# logmega_083.net
KiCad netlist of a schematic drawn in EAGLE
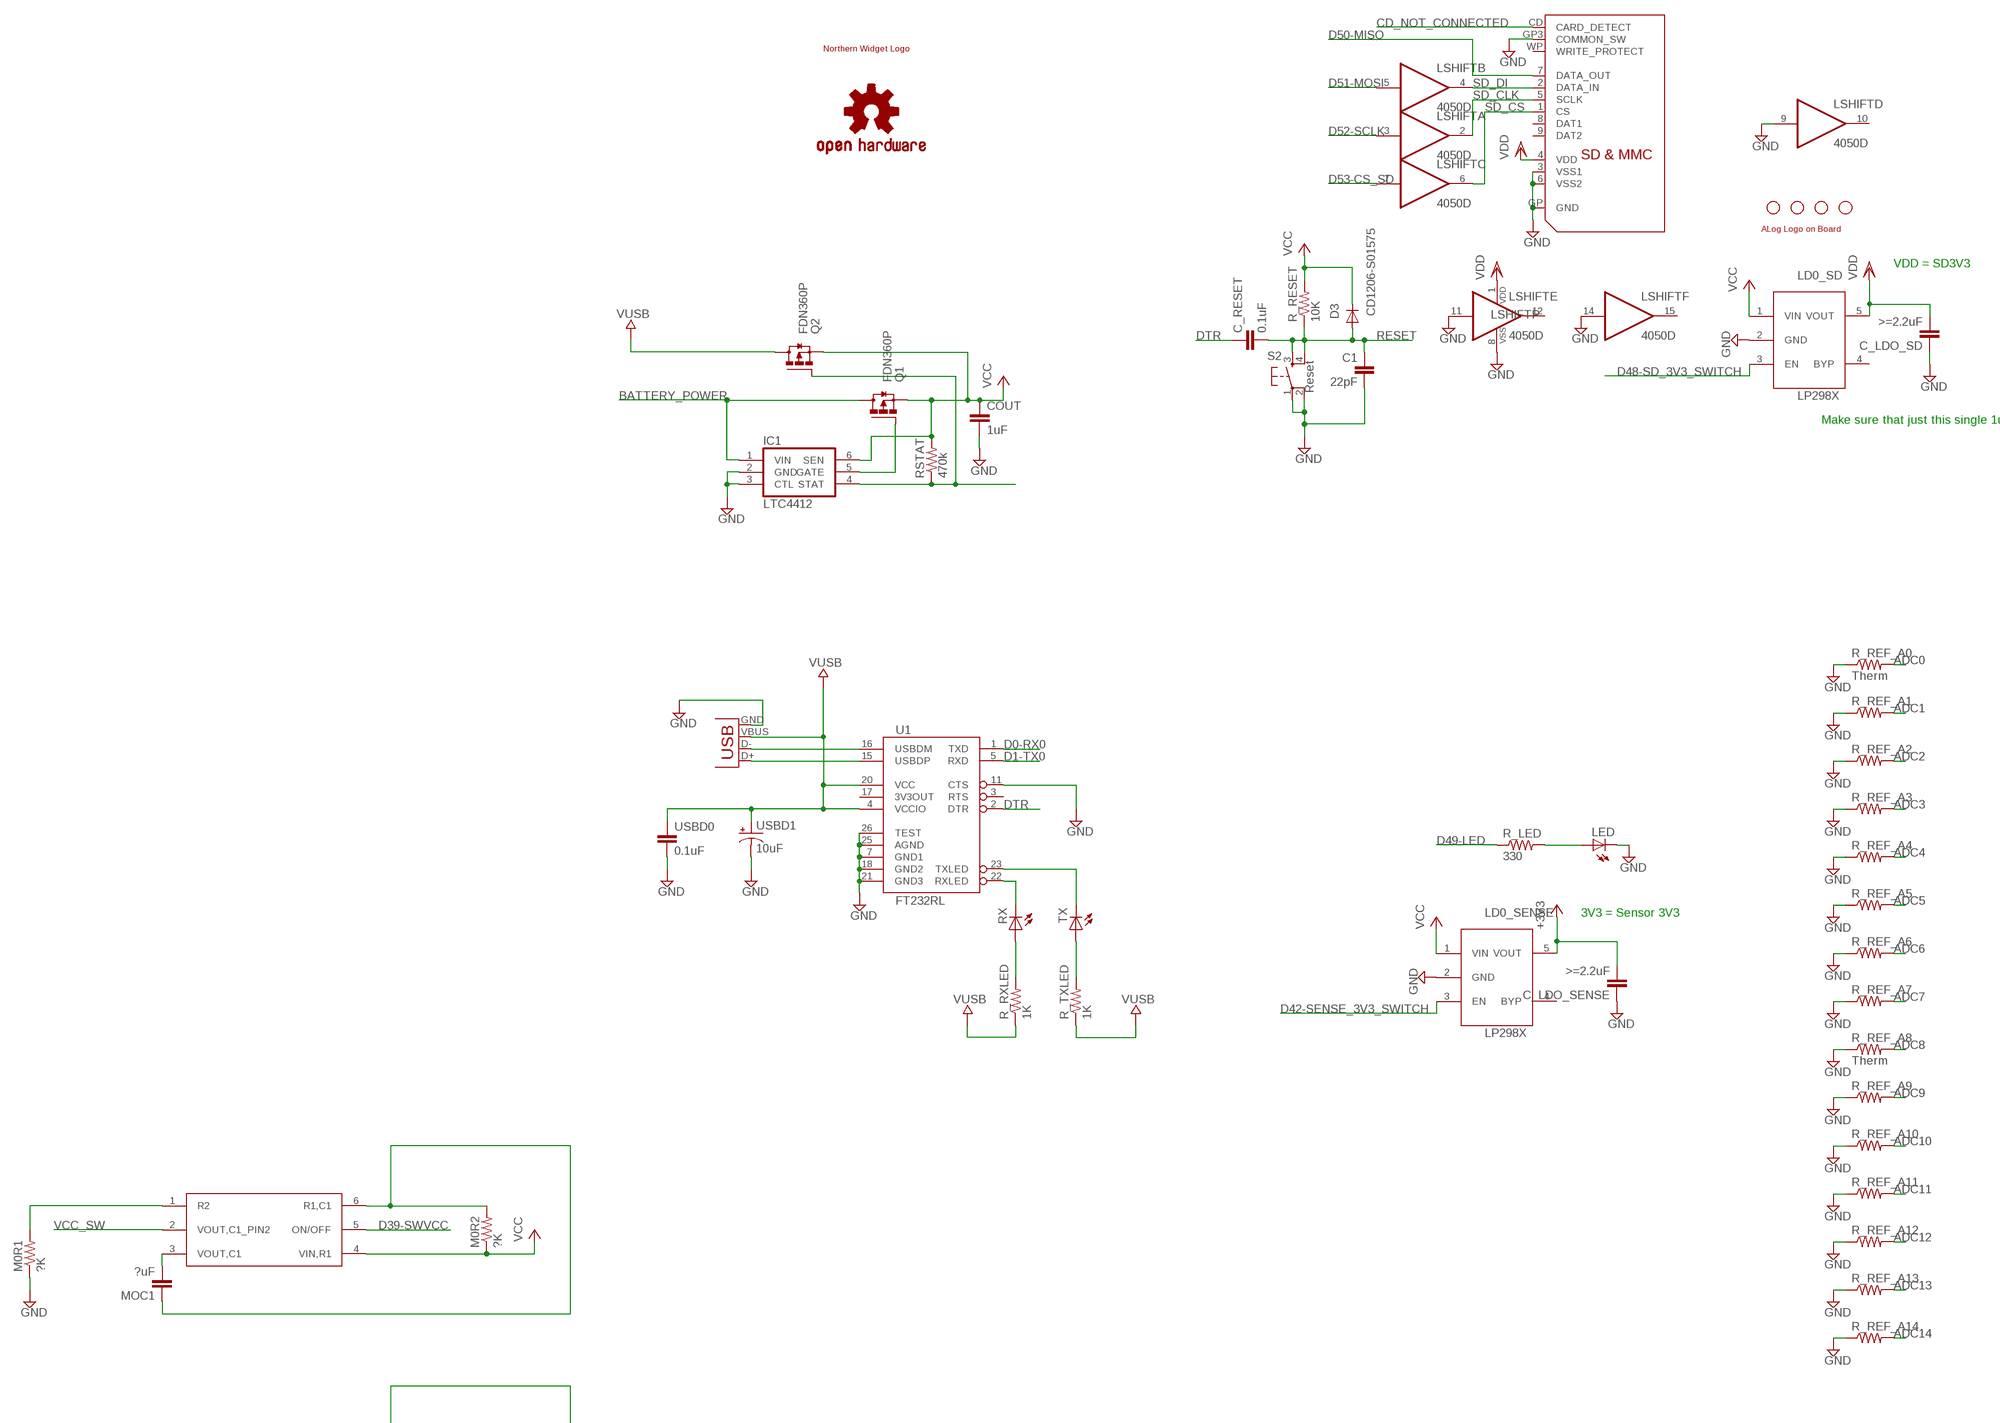
[diagram p0: schematic, sheet 1, part 1 of 3]
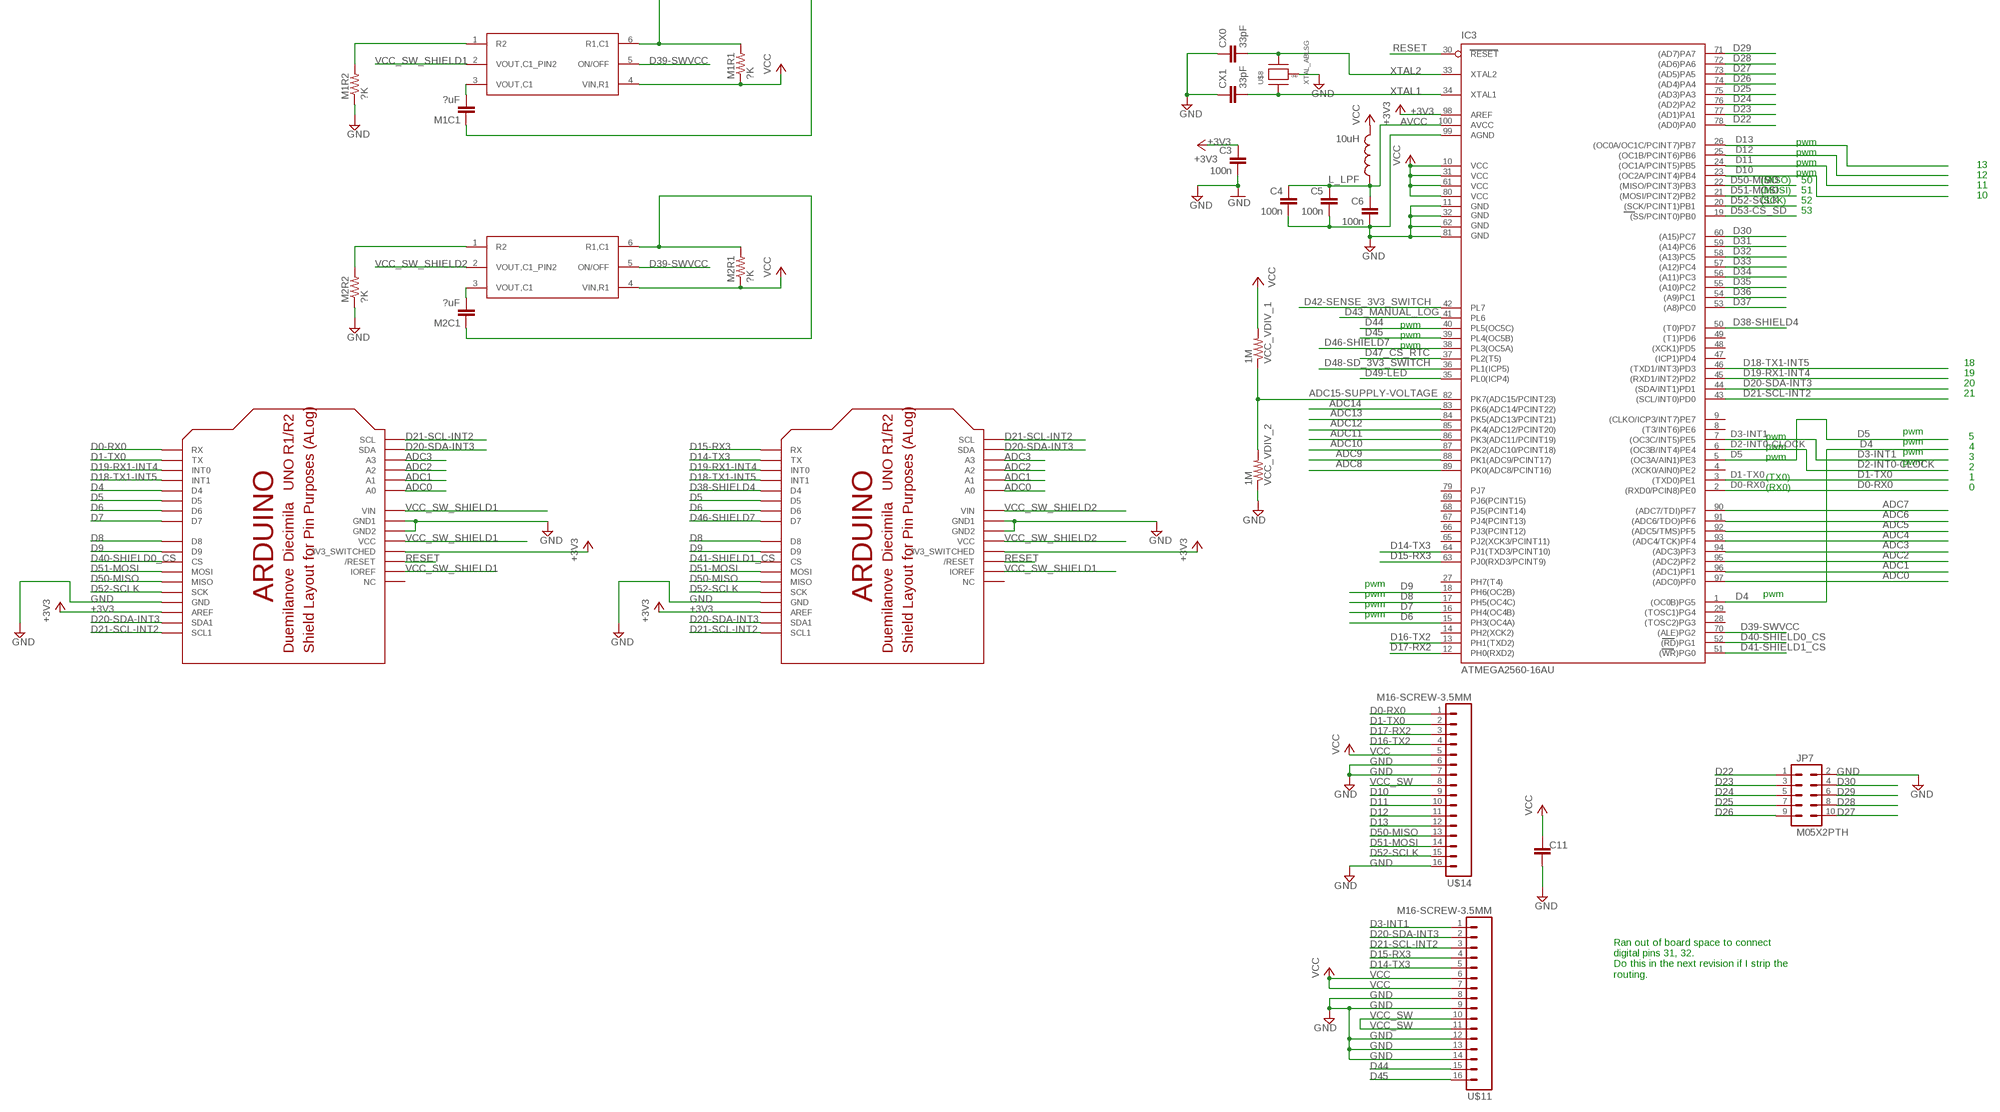
[diagram p1: schematic, sheet 1, part 2 of 3]
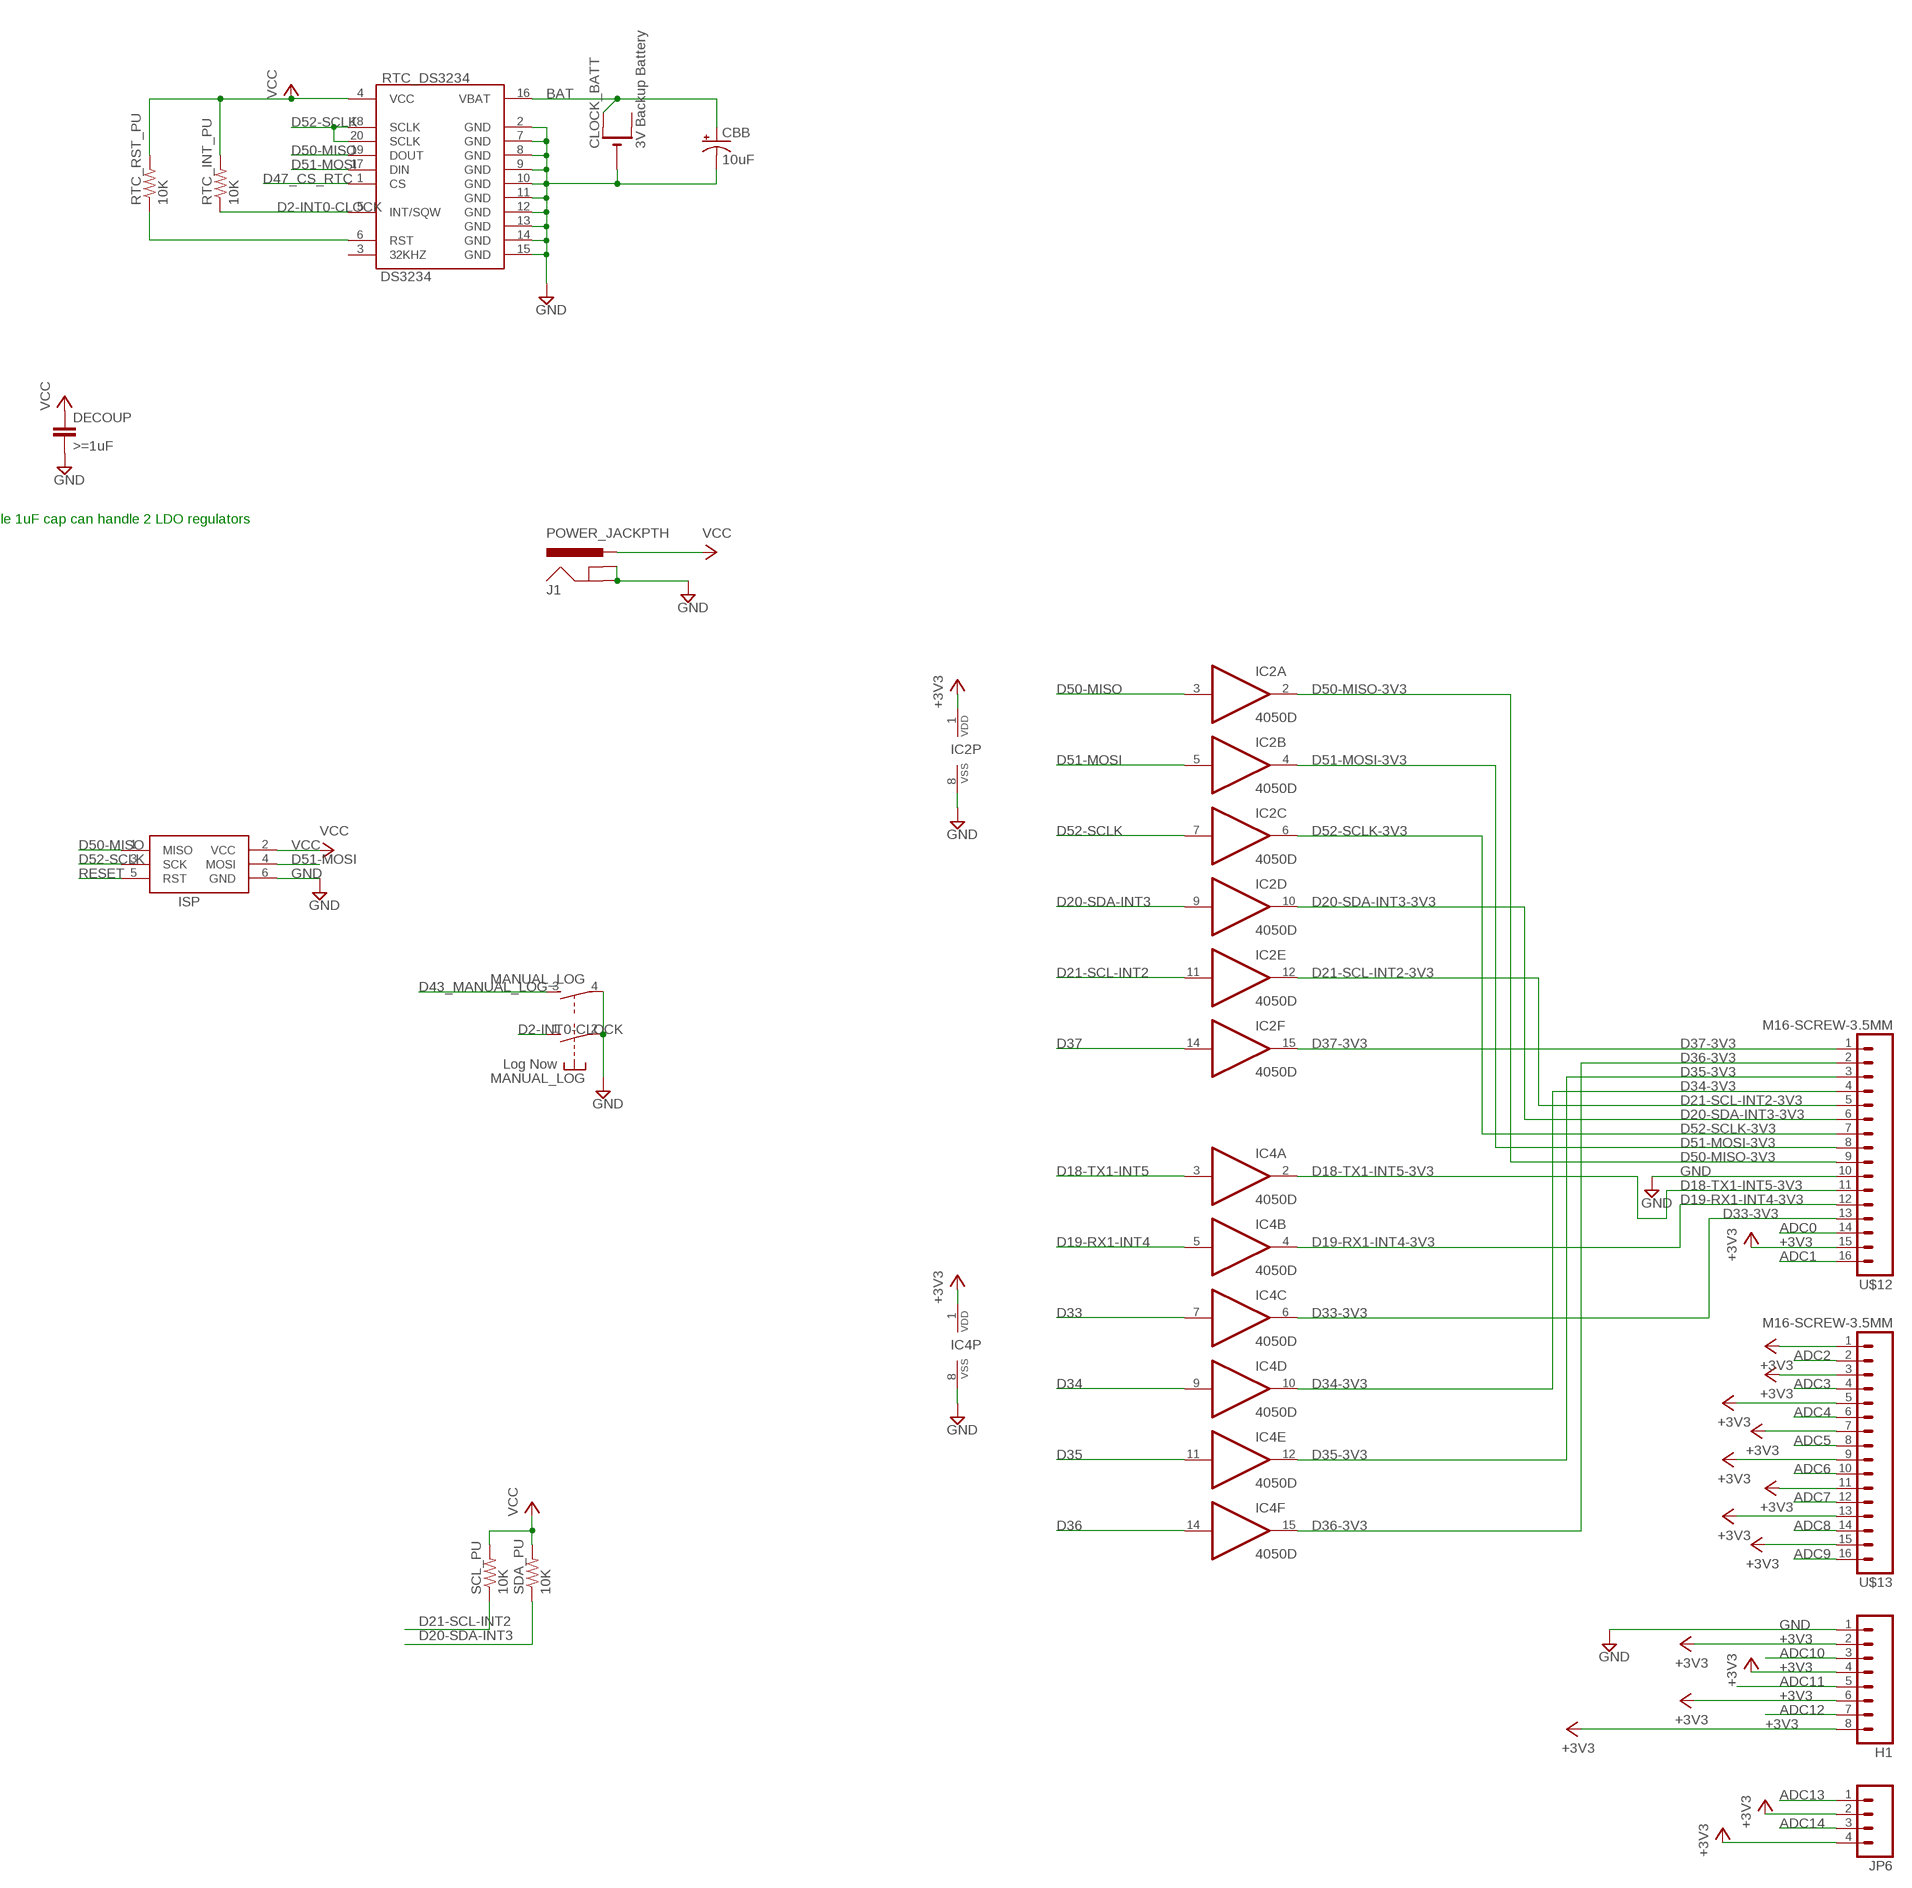
[diagram p2: schematic, sheet 1, part 3 of 3]

(export (version "E")
  (design (tool "Eeschema 10.0.6"))
  (components
    (comp (ref "C1")
      (value "22pF")
      (footprint "eagle-import:C0603-ROUND")
      (libsource (lib "eagle-import") (part "C-EU0603-RND"))
    )
    (comp (ref "C3")
      (value "100n")
      (footprint "eagle-import:C0603-ROUND")
      (libsource (lib "eagle-import") (part "C-EU0603-RND"))
    )
    (comp (ref "C4")
      (value "100n")
      (footprint "eagle-import:C0603-ROUND")
      (libsource (lib "eagle-import") (part "C-EU0603-RND"))
    )
    (comp (ref "C5")
      (value "100n")
      (footprint "eagle-import:C0603-ROUND")
      (libsource (lib "eagle-import") (part "C-EU0603-RND"))
    )
    (comp (ref "C6")
      (value "100n")
      (footprint "eagle-import:C0603-ROUND")
      (libsource (lib "eagle-import") (part "C-EU0603-RND"))
    )
    (comp (ref "C11")
      (value "100n")
      (footprint "eagle-import:C0603-ROUND")
      (libsource (lib "eagle-import") (part "C-EU0603-RND"))
    )
    (comp (ref "CBB")
      (value "10uF")
      (footprint "eagle-import:EIA3216")
      (libsource (lib "eagle-import") (part "CAP_POL1206"))
    )
    (comp (ref "CLOCK_BATT")
      (value "3V Backup Battery")
      (footprint "eagle-import:CR2032-SMD")
      (libsource (lib "eagle-import") (part "CR2032SMT"))
    )
    (comp (ref "COUT")
      (value "1uF")
      (footprint "eagle-import:C0603-ROUND")
      (libsource (lib "eagle-import") (part "C-EUC0603"))
    )
    (comp (ref "CX0")
      (value "33pF")
      (footprint "eagle-import:C0603")
      (libsource (lib "eagle-import") (part "resistor_C-EUC0603"))
    )
    (comp (ref "CX1")
      (value "33pF")
      (footprint "eagle-import:C0603")
      (libsource (lib "eagle-import") (part "resistor_C-EUC0603"))
    )
    (comp (ref "C_LDO_SD")
      (value ">=2.2uF")
      (footprint "eagle-import:C0603")
      (libsource (lib "eagle-import") (part "resistor_C-EUC0603"))
    )
    (comp (ref "C_LDO_SENSE")
      (value ">=2.2uF")
      (footprint "eagle-import:C0603")
      (libsource (lib "eagle-import") (part "resistor_C-EUC0603"))
    )
    (comp (ref "C_RESET")
      (value "0.1uF")
      (footprint "eagle-import:C0603")
      (libsource (lib "eagle-import") (part "resistor_C-EUC0603"))
    )
    (comp (ref "D3")
      (value "CD1206-S01575")
      (footprint "eagle-import:MINIMELF")
      (libsource (lib "eagle-import") (part "DIODE-MINIMELF"))
    )
    (comp (ref "DECOUP")
      (value ">=1uF")
      (footprint "eagle-import:C0603")
      (libsource (lib "eagle-import") (part "resistor_C-EUC0603"))
    )
    (comp (ref "H1")
      (value "M083.5MM-8")
      (footprint "eagle-import:SCREWTERMINAL-3.5MM-8")
      (libsource (lib "eagle-import") (part "M083.5MM-8"))
    )
    (comp (ref "IC1")
      (value "LTC4412")
      (footprint "eagle-import:TSOT23-6")
      (libsource (lib "eagle-import") (part "LTC4412S6E"))
    )
    (comp (ref "IC2")
      (value "4050D")
      (footprint "eagle-import:SO16")
      (libsource (lib "eagle-import") (part "4050D"))
    )
    (comp (ref "IC3")
      (value "ATMEGA2560-16AU")
      (footprint "eagle-import:TQFP100")
      (libsource (lib "eagle-import") (part "ATMEGA2560AU2560-16"))
    )
    (comp (ref "IC4")
      (value "4050D")
      (footprint "eagle-import:SO16")
      (libsource (lib "eagle-import") (part "4050D"))
    )
    (comp (ref "ISP")
      (value "AVRISP-6")
      (footprint "eagle-import:AVRISP")
      (libsource (lib "eagle-import") (part "AVRISP-6"))
    )
    (comp (ref "J1")
      (value "POWER_JACKPTH")
      (footprint "eagle-import:POWER_JACK_PTH")
      (libsource (lib "eagle-import") (part "POWER_JACKPTH"))
    )
    (comp (ref "JP1")
      (value "STAND-OFF")
      (footprint "eagle-import:STAND-OFF")
      (libsource (lib "eagle-import") (part "STAND-OFF"))
    )
    (comp (ref "JP2")
      (value "STAND-OFF")
      (footprint "eagle-import:STAND-OFF")
      (libsource (lib "eagle-import") (part "STAND-OFF"))
    )
    (comp (ref "JP3")
      (value "STAND-OFF")
      (footprint "eagle-import:STAND-OFF")
      (libsource (lib "eagle-import") (part "STAND-OFF"))
    )
    (comp (ref "JP4")
      (value "STAND-OFF")
      (footprint "eagle-import:STAND-OFF")
      (libsource (lib "eagle-import") (part "STAND-OFF"))
    )
    (comp (ref "JP5")
      (value "USB-B")
      (footprint "eagle-import:USB-B-PTH")
      (libsource (lib "eagle-import") (part "USBPTH"))
    )
    (comp (ref "JP6")
      (value "M04SCREW")
      (footprint "eagle-import:SCREWTERMINAL-3.5MM-4")
      (libsource (lib "eagle-import") (part "M04SCREW"))
    )
    (comp (ref "JP7")
      (value "M05X2PTH")
      (footprint "eagle-import:AVR_ICSP")
      (libsource (lib "eagle-import") (part "M05X2PTH"))
    )
    (comp (ref "LD0_SD")
      (value "LP2985")
      (footprint "eagle-import:SOT23-5L")
      (libsource (lib "eagle-import") (part "LP298XS"))
    )
    (comp (ref "LD0_SENSE")
      (value "LP2985")
      (footprint "eagle-import:SOT23-5L")
      (libsource (lib "eagle-import") (part "LP298XS"))
    )
    (comp (ref "LED")
      (value "LED3MM")
      (footprint "eagle-import:LED3MM")
      (libsource (lib "eagle-import") (part "LED3MM"))
    )
    (comp (ref "LOGO1")
      (value "OSHW-LOGOM")
      (footprint "eagle-import:OSHW-LOGO-M")
      (libsource (lib "eagle-import") (part "OSHW-LOGOM"))
    )
    (comp (ref "LSHIFT")
      (value "4050D")
      (footprint "eagle-import:SO16")
      (libsource (lib "eagle-import") (part "4050D"))
    )
    (comp (ref "L_LPF")
      (value "10uH")
      (footprint "eagle-import:0805")
      (libsource (lib "eagle-import") (part "INDUCTOR0805"))
    )
    (comp (ref "M0R1")
      (value "?K")
      (footprint "eagle-import:R0603")
      (libsource (lib "eagle-import") (part "R-US_R0603"))
    )
    (comp (ref "M0R2")
      (value "?K")
      (footprint "eagle-import:R0603")
      (libsource (lib "eagle-import") (part "R-US_R0603"))
    )
    (comp (ref "M1")
      (value "FDG6342L")
      (footprint "eagle-import:SOT-363")
      (libsource (lib "eagle-import") (part "FDG6342L"))
    )
    (comp (ref "M1C1")
      (value "?uF")
      (footprint "eagle-import:C0603")
      (libsource (lib "eagle-import") (part "resistor_C-EUC0603"))
    )
    (comp (ref "M1R1")
      (value "?K")
      (footprint "eagle-import:R0603")
      (libsource (lib "eagle-import") (part "R-US_R0603"))
    )
    (comp (ref "M1R2")
      (value "?K")
      (footprint "eagle-import:R0603")
      (libsource (lib "eagle-import") (part "R-US_R0603"))
    )
    (comp (ref "M2")
      (value "FDG6342L")
      (footprint "eagle-import:SOT-363")
      (libsource (lib "eagle-import") (part "FDG6342L"))
    )
    (comp (ref "M2C1")
      (value "?uF")
      (footprint "eagle-import:C0603")
      (libsource (lib "eagle-import") (part "resistor_C-EUC0603"))
    )
    (comp (ref "M2R1")
      (value "?K")
      (footprint "eagle-import:R0603")
      (libsource (lib "eagle-import") (part "R-US_R0603"))
    )
    (comp (ref "M2R2")
      (value "?K")
      (footprint "eagle-import:R0603")
      (libsource (lib "eagle-import") (part "R-US_R0603"))
    )
    (comp (ref "MANUAL_LOG")
      (value "Log Now")
      (footprint "eagle-import:PVA1F")
      (libsource (lib "eagle-import") (part "PVA1"))
    )
    (comp (ref "MOC1")
      (value "?uF")
      (footprint "eagle-import:C0603")
      (libsource (lib "eagle-import") (part "resistor_C-EUC0603"))
    )
    (comp (ref "Q1")
      (value "FDN360P")
      (footprint "eagle-import:SUPER-SOT3")
      (libsource (lib "eagle-import") (part "FDN360P"))
    )
    (comp (ref "Q2")
      (value "FDN360P")
      (footprint "eagle-import:SUPER-SOT3")
      (libsource (lib "eagle-import") (part "FDN360P"))
    )
    (comp (ref "RSTAT")
      (value "470k")
      (footprint "eagle-import:R0603")
      (libsource (lib "eagle-import") (part "R-US_R0603"))
    )
    (comp (ref "RTC_DS3234")
      (value "DS3234")
      (footprint "eagle-import:DS3234")
      (libsource (lib "eagle-import") (part "DS3234"))
    )
    (comp (ref "RTC_INT_PU")
      (value "10K")
      (footprint "eagle-import:R0603")
      (libsource (lib "eagle-import") (part "R-US_R0603"))
    )
    (comp (ref "RTC_RST_PU")
      (value "10K")
      (footprint "eagle-import:R0603")
      (libsource (lib "eagle-import") (part "R-US_R0603"))
    )
    (comp (ref "RX")
      (value "LED0603")
      (footprint "eagle-import:LED-0603")
      (libsource (lib "eagle-import") (part "SparkFun-LED_LED0603"))
    )
    (comp (ref "R_LED")
      (value "330")
      (footprint "eagle-import:R0603")
      (libsource (lib "eagle-import") (part "R-US_R0603"))
    )
    (comp (ref "R_REF_A0")
      (value "Therm")
      (footprint "eagle-import:0207_10")
      (libsource (lib "eagle-import") (part "resistor_R-US_0207/10"))
    )
    (comp (ref "R_REF_A1")
      (value "R-US_0207/10")
      (footprint "eagle-import:0207_10")
      (libsource (lib "eagle-import") (part "resistor_R-US_0207/10"))
    )
    (comp (ref "R_REF_A2")
      (value "R-US_0207/10")
      (footprint "eagle-import:0207_10")
      (libsource (lib "eagle-import") (part "resistor_R-US_0207/10"))
    )
    (comp (ref "R_REF_A3")
      (value "R-US_0207/10")
      (footprint "eagle-import:0207_10")
      (libsource (lib "eagle-import") (part "resistor_R-US_0207/10"))
    )
    (comp (ref "R_REF_A4")
      (value "R-US_0207/10")
      (footprint "eagle-import:0207_10")
      (libsource (lib "eagle-import") (part "resistor_R-US_0207/10"))
    )
    (comp (ref "R_REF_A5")
      (value "R-US_0207/10")
      (footprint "eagle-import:0207_10")
      (libsource (lib "eagle-import") (part "resistor_R-US_0207/10"))
    )
    (comp (ref "R_REF_A6")
      (value "R-US_0207/10")
      (footprint "eagle-import:0207_10")
      (libsource (lib "eagle-import") (part "resistor_R-US_0207/10"))
    )
    (comp (ref "R_REF_A7")
      (value "R-US_0207/10")
      (footprint "eagle-import:0207_10")
      (libsource (lib "eagle-import") (part "resistor_R-US_0207/10"))
    )
    (comp (ref "R_REF_A8")
      (value "Therm")
      (footprint "eagle-import:0207_10")
      (libsource (lib "eagle-import") (part "resistor_R-US_0207/10"))
    )
    (comp (ref "R_REF_A9")
      (value "R-US_0207/10")
      (footprint "eagle-import:0207_10")
      (libsource (lib "eagle-import") (part "resistor_R-US_0207/10"))
    )
    (comp (ref "R_REF_A10")
      (value "R-US_0207/10")
      (footprint "eagle-import:0207_10")
      (libsource (lib "eagle-import") (part "resistor_R-US_0207/10"))
    )
    (comp (ref "R_REF_A11")
      (value "R-US_0207/10")
      (footprint "eagle-import:0207_10")
      (libsource (lib "eagle-import") (part "resistor_R-US_0207/10"))
    )
    (comp (ref "R_REF_A12")
      (value "R-US_0207/10")
      (footprint "eagle-import:0207_10")
      (libsource (lib "eagle-import") (part "resistor_R-US_0207/10"))
    )
    (comp (ref "R_REF_A13")
      (value "R-US_0207/10")
      (footprint "eagle-import:0207_10")
      (libsource (lib "eagle-import") (part "resistor_R-US_0207/10"))
    )
    (comp (ref "R_REF_A14")
      (value "R-US_0207/10")
      (footprint "eagle-import:0207_10")
      (libsource (lib "eagle-import") (part "resistor_R-US_0207/10"))
    )
    (comp (ref "R_RESET")
      (value "10K")
      (footprint "eagle-import:R0603")
      (libsource (lib "eagle-import") (part "R-US_R0603"))
    )
    (comp (ref "R_RXLED")
      (value "1K")
      (footprint "eagle-import:R0603")
      (libsource (lib "eagle-import") (part "R-US_R0603"))
    )
    (comp (ref "R_TXLED")
      (value "1K")
      (footprint "eagle-import:R0603")
      (libsource (lib "eagle-import") (part "R-US_R0603"))
    )
    (comp (ref "S2")
      (value "Reset")
      (footprint "eagle-import:TACTILE-PTH")
      (libsource (lib "eagle-import") (part "TAC_SWITCHPTH"))
    )
    (comp (ref "SCL_PU")
      (value "10K")
      (footprint "eagle-import:R0603")
      (libsource (lib "eagle-import") (part "R-US_R0603"))
    )
    (comp (ref "SD")
      (value "SDMMC06132")
      (footprint "eagle-import:06132")
      (libsource (lib "eagle-import") (part "SDMMC06132"))
    )
    (comp (ref "SDA_PU")
      (value "10K")
      (footprint "eagle-import:R0603")
      (libsource (lib "eagle-import") (part "R-US_R0603"))
    )
    (comp (ref "SW")
      (value "FDG6342L")
      (footprint "eagle-import:SOT-363")
      (libsource (lib "eagle-import") (part "FDG6342L"))
    )
    (comp (ref "TX")
      (value "LED0603")
      (footprint "eagle-import:LED-0603")
      (libsource (lib "eagle-import") (part "SparkFun-LED_LED0603"))
    )
    (comp (ref "U$1")
      (value "NWLOGO")
      (footprint "eagle-import:NWLOGO")
      (libsource (lib "eagle-import") (part "NWLOGO"))
    )
    (comp (ref "U$2")
      (value "ALOG_LOGO_V1_5.5MM")
      (footprint "eagle-import:ALOG_LOGO_V1_SMALL")
      (libsource (lib "eagle-import") (part "ALOG_LOGO_V1_5.5MM"))
    )
    (comp (ref "U$7")
      (value "ARDUINO_SHIELD_BIGLOG_2")
      (footprint "eagle-import:ARDUINO_SHIELD_PO_BL2")
      (libsource (lib "eagle-import") (part "ARDUINO_SHIELD_BIGLOG_2"))
    )
    (comp (ref "U$8")
      (value "XTAL_ABLSG")
      (footprint "eagle-import:AT49")
      (libsource (lib "eagle-import") (part "XTAL_ABLSG"))
    )
    (comp (ref "U$9")
      (value "ARDUINO_SHIELD_BIGLOG_1")
      (footprint "eagle-import:ARDUINO_SHIELD_PO_BL1")
      (libsource (lib "eagle-import") (part "ARDUINO_SHIELD_BIGLOG_1"))
    )
    (comp (ref "U$11")
      (value "M16-SCREW-3.5MM")
      (footprint "eagle-import:M16-SCREW-3.5MM")
      (libsource (lib "eagle-import") (part "M16-SCREW-3.5MM"))
    )
    (comp (ref "U$12")
      (value "M16-SCREW-3.5MM")
      (footprint "eagle-import:M16-SCREW-3.5MM")
      (libsource (lib "eagle-import") (part "M16-SCREW-3.5MM"))
    )
    (comp (ref "U$13")
      (value "M16-SCREW-3.5MM")
      (footprint "eagle-import:M16-SCREW-3.5MM")
      (libsource (lib "eagle-import") (part "M16-SCREW-3.5MM"))
    )
    (comp (ref "U$14")
      (value "M16-SCREW-3.5MM")
      (footprint "eagle-import:M16-SCREW-3.5MM")
      (libsource (lib "eagle-import") (part "M16-SCREW-3.5MM"))
    )
    (comp (ref "U1")
      (value "FT232RL")
      (footprint "eagle-import:SSOP28DB")
      (libsource (lib "eagle-import") (part "FT232RL-BASICSSOP"))
    )
    (comp (ref "USBD0")
      (value "0.1uF")
      (footprint "eagle-import:C0603")
      (libsource (lib "eagle-import") (part "resistor_C-EUC0603"))
    )
    (comp (ref "USBD1")
      (value "10uF")
      (footprint "eagle-import:EIA3216")
      (libsource (lib "eagle-import") (part "CAP_POL1206"))
    )
    (comp (ref "VCC_VDIV_1")
      (value "1M")
      (footprint "eagle-import:R0603")
      (libsource (lib "eagle-import") (part "R-US_R0603"))
    )
    (comp (ref "VCC_VDIV_2")
      (value "1M")
      (footprint "eagle-import:R0603")
      (libsource (lib "eagle-import") (part "R-US_R0603"))
    )
  )
  (nets
    (net (code "1") (name "+3V3") (class "Default")
      (node (ref "C3") (pin "1") (pinfunction "1_1") (pintype "passive"))
      (node (ref "C_LDO_SENSE") (pin "2") (pinfunction "2_2") (pintype "passive"))
      (node (ref "H1") (pin "2") (pinfunction "2_2") (pintype "passive"))
      (node (ref "H1") (pin "4") (pinfunction "4_4") (pintype "passive"))
      (node (ref "H1") (pin "6") (pinfunction "6_6") (pintype "passive"))
      (node (ref "H1") (pin "8") (pinfunction "8_8") (pintype "passive"))
      (node (ref "IC2") (pin "1") (pinfunction "VDD_1") (pintype "power_in"))
      (node (ref "IC3") (pin "98") (pinfunction "AREF_98") (pintype "bidirectional"))
      (node (ref "IC4") (pin "1") (pinfunction "VDD_1") (pintype "power_in"))
      (node (ref "JP6") (pin "2") (pinfunction "2_2") (pintype "passive"))
      (node (ref "JP6") (pin "4") (pinfunction "4_4") (pintype "passive"))
      (node (ref "LD0_SENSE") (pin "5") (pinfunction "VOUT_5") (pintype "bidirectional"))
      (node (ref "U$12") (pin "15") (pinfunction "15_15") (pintype "passive"))
      (node (ref "U$13") (pin "1") (pinfunction "1_1") (pintype "passive"))
      (node (ref "U$13") (pin "11") (pinfunction "11_11") (pintype "passive"))
      (node (ref "U$13") (pin "13") (pinfunction "13_13") (pintype "passive"))
      (node (ref "U$13") (pin "15") (pinfunction "15_15") (pintype "passive"))
      (node (ref "U$13") (pin "3") (pinfunction "3_3") (pintype "passive"))
      (node (ref "U$13") (pin "5") (pinfunction "5_5") (pintype "passive"))
      (node (ref "U$13") (pin "7") (pinfunction "7_7") (pintype "passive"))
      (node (ref "U$13") (pin "9") (pinfunction "9_9") (pintype "passive"))
      (node (ref "U$7") (pin "3.3V") (pinfunction "3V3_SWITCHED_3.3V") (pintype "power_in"))
      (node (ref "U$7") (pin "AREF") (pinfunction "AREF_AREF") (pintype "bidirectional"))
      (node (ref "U$9") (pin "3.3V") (pinfunction "3V3_SWITCHED_3.3V") (pintype "power_in"))
      (node (ref "U$9") (pin "AREF") (pinfunction "AREF_AREF") (pintype "bidirectional"))
    )
    (net (code "2") (name "/ADC0") (class "Default")
      (node (ref "IC3") (pin "97") (pinfunction "(ADC0)PF0_97") (pintype "bidirectional"))
      (node (ref "R_REF_A0") (pin "2") (pinfunction "2_2") (pintype "passive"))
      (node (ref "U$12") (pin "14") (pinfunction "14_14") (pintype "passive"))
      (node (ref "U$7") (pin "A0") (pinfunction "A0_A0") (pintype "bidirectional"))
      (node (ref "U$9") (pin "A0") (pinfunction "A0_A0") (pintype "bidirectional"))
    )
    (net (code "3") (name "/ADC1") (class "Default")
      (node (ref "IC3") (pin "96") (pinfunction "(ADC1)PF1_96") (pintype "bidirectional"))
      (node (ref "R_REF_A1") (pin "2") (pinfunction "2_2") (pintype "passive"))
      (node (ref "U$12") (pin "16") (pinfunction "16_16") (pintype "passive"))
      (node (ref "U$7") (pin "A1") (pinfunction "A1_A1") (pintype "bidirectional"))
      (node (ref "U$9") (pin "A1") (pinfunction "A1_A1") (pintype "bidirectional"))
    )
    (net (code "4") (name "/ADC2") (class "Default")
      (node (ref "IC3") (pin "95") (pinfunction "(ADC2)PF2_95") (pintype "bidirectional"))
      (node (ref "R_REF_A2") (pin "2") (pinfunction "2_2") (pintype "passive"))
      (node (ref "U$13") (pin "2") (pinfunction "2_2") (pintype "passive"))
      (node (ref "U$7") (pin "A2") (pinfunction "A2_A2") (pintype "bidirectional"))
      (node (ref "U$9") (pin "A2") (pinfunction "A2_A2") (pintype "bidirectional"))
    )
    (net (code "5") (name "/ADC3") (class "Default")
      (node (ref "IC3") (pin "94") (pinfunction "(ADC3)PF3_94") (pintype "bidirectional"))
      (node (ref "R_REF_A3") (pin "2") (pinfunction "2_2") (pintype "passive"))
      (node (ref "U$13") (pin "4") (pinfunction "4_4") (pintype "passive"))
      (node (ref "U$7") (pin "A3") (pinfunction "A3_A3") (pintype "bidirectional"))
      (node (ref "U$9") (pin "A3") (pinfunction "A3_A3") (pintype "bidirectional"))
    )
    (net (code "6") (name "/ADC4") (class "Default")
      (node (ref "IC3") (pin "93") (pinfunction "(ADC4/TCK)PF4_93") (pintype "bidirectional"))
      (node (ref "R_REF_A4") (pin "2") (pinfunction "2_2") (pintype "passive"))
      (node (ref "U$13") (pin "6") (pinfunction "6_6") (pintype "passive"))
    )
    (net (code "7") (name "/ADC5") (class "Default")
      (node (ref "IC3") (pin "92") (pinfunction "(ADC5/TMS)PF5_92") (pintype "bidirectional"))
      (node (ref "R_REF_A5") (pin "2") (pinfunction "2_2") (pintype "passive"))
      (node (ref "U$13") (pin "8") (pinfunction "8_8") (pintype "passive"))
    )
    (net (code "8") (name "/ADC6") (class "Default")
      (node (ref "IC3") (pin "91") (pinfunction "(ADC6/TDO)PF6_91") (pintype "bidirectional"))
      (node (ref "R_REF_A6") (pin "2") (pinfunction "2_2") (pintype "passive"))
      (node (ref "U$13") (pin "10") (pinfunction "10_10") (pintype "passive"))
    )
    (net (code "9") (name "/ADC7") (class "Default")
      (node (ref "IC3") (pin "90") (pinfunction "(ADC7/TDI)PF7_90") (pintype "bidirectional"))
      (node (ref "R_REF_A7") (pin "2") (pinfunction "2_2") (pintype "passive"))
      (node (ref "U$13") (pin "12") (pinfunction "12_12") (pintype "passive"))
    )
    (net (code "10") (name "/ADC8") (class "Default")
      (node (ref "IC3") (pin "89") (pinfunction "PK0(ADC8/PCINT16)_89") (pintype "bidirectional"))
      (node (ref "R_REF_A8") (pin "2") (pinfunction "2_2") (pintype "passive"))
      (node (ref "U$13") (pin "14") (pinfunction "14_14") (pintype "passive"))
    )
    (net (code "11") (name "/ADC9") (class "Default")
      (node (ref "IC3") (pin "88") (pinfunction "PK1(ADC9/PCINT17)_88") (pintype "bidirectional"))
      (node (ref "R_REF_A9") (pin "2") (pinfunction "2_2") (pintype "passive"))
      (node (ref "U$13") (pin "16") (pinfunction "16_16") (pintype "passive"))
    )
    (net (code "12") (name "/ADC10") (class "Default")
      (node (ref "H1") (pin "3") (pinfunction "3_3") (pintype "passive"))
      (node (ref "IC3") (pin "87") (pinfunction "PK2(ADC10/PCINT18)_87") (pintype "bidirectional"))
      (node (ref "R_REF_A10") (pin "2") (pinfunction "2_2") (pintype "passive"))
    )
    (net (code "13") (name "/ADC11") (class "Default")
      (node (ref "H1") (pin "5") (pinfunction "5_5") (pintype "passive"))
      (node (ref "IC3") (pin "86") (pinfunction "PK3(ADC11/PCINT19)_86") (pintype "bidirectional"))
      (node (ref "R_REF_A11") (pin "2") (pinfunction "2_2") (pintype "passive"))
    )
    (net (code "14") (name "/ADC12") (class "Default")
      (node (ref "H1") (pin "7") (pinfunction "7_7") (pintype "passive"))
      (node (ref "IC3") (pin "85") (pinfunction "PK4(ADC12/PCINT20)_85") (pintype "bidirectional"))
      (node (ref "R_REF_A12") (pin "2") (pinfunction "2_2") (pintype "passive"))
    )
    (net (code "15") (name "/ADC13") (class "Default")
      (node (ref "IC3") (pin "84") (pinfunction "PK5(ADC13/PCINT21)_84") (pintype "bidirectional"))
      (node (ref "JP6") (pin "1") (pinfunction "1_1") (pintype "passive"))
      (node (ref "R_REF_A13") (pin "2") (pinfunction "2_2") (pintype "passive"))
    )
    (net (code "16") (name "/ADC14") (class "Default")
      (node (ref "IC3") (pin "83") (pinfunction "PK6(ADC14/PCINT22)_83") (pintype "bidirectional"))
      (node (ref "JP6") (pin "3") (pinfunction "3_3") (pintype "passive"))
      (node (ref "R_REF_A14") (pin "2") (pinfunction "2_2") (pintype "passive"))
    )
    (net (code "17") (name "/ADC15-SUPPLY-VOLTAGE") (class "Default")
      (node (ref "IC3") (pin "82") (pinfunction "PK7(ADC15/PCINT23)_82") (pintype "bidirectional"))
      (node (ref "VCC_VDIV_1") (pin "1") (pinfunction "1_1") (pintype "passive"))
      (node (ref "VCC_VDIV_2") (pin "2") (pinfunction "2_2") (pintype "passive"))
    )
    (net (code "18") (name "/AVCC") (class "Default")
      (node (ref "C4") (pin "1") (pinfunction "1_1") (pintype "passive"))
      (node (ref "C5") (pin "1") (pinfunction "1_1") (pintype "passive"))
      (node (ref "C6") (pin "1") (pinfunction "1_1") (pintype "passive"))
      (node (ref "IC3") (pin "100") (pinfunction "AVCC_100") (pintype "power_in"))
      (node (ref "L_LPF") (pin "1") (pinfunction "1_1") (pintype "passive"))
    )
    (net (code "19") (name "/BAT") (class "Default")
      (node (ref "CBB") (pin "A") (pinfunction "+_A") (pintype "passive"))
      (node (ref "CLOCK_BATT") (pin "+$1") (pinfunction "+_+$1") (pintype "passive"))
      (node (ref "RTC_DS3234") (pin "16") (pinfunction "VBAT_16") (pintype "bidirectional"))
    )
    (net (code "20") (name "/BATTERY_POWER") (class "Default")
      (node (ref "IC1") (pin "1") (pinfunction "VIN_1") (pintype "input"))
      (node (ref "Q1") (pin "3") (pinfunction "D_3") (pintype "passive"))
    )
    (net (code "21") (name "/CD_NOT_CONNECTED") (class "Default")
      (node (ref "SD") (pin "CD") (pinfunction "CARD_DETECT_CD") (pintype "passive"))
    )
    (net (code "22") (name "/D0-RX0") (class "Default")
      (node (ref "IC3") (pin "2") (pinfunction "(RXD0/PCIN8)PE0_2") (pintype "bidirectional"))
      (node (ref "U$14") (pin "1") (pinfunction "1_1") (pintype "passive"))
      (node (ref "U$9") (pin "RX") (pinfunction "RX_RX") (pintype "bidirectional"))
      (node (ref "U1") (pin "1") (pinfunction "TXD_1") (pintype "output"))
    )
    (net (code "23") (name "/D1-TX0") (class "Default")
      (node (ref "IC3") (pin "3") (pinfunction "(TXD0)PE1_3") (pintype "bidirectional"))
      (node (ref "U$14") (pin "2") (pinfunction "2_2") (pintype "passive"))
      (node (ref "U$9") (pin "TX") (pinfunction "TX_TX") (pintype "bidirectional"))
      (node (ref "U1") (pin "5") (pinfunction "RXD_5") (pintype "input"))
    )
    (net (code "24") (name "/D2-INT0-CLOCK") (class "Default")
      (node (ref "IC3") (pin "6") (pinfunction "(OC3B/INT4)PE4_6") (pintype "bidirectional"))
      (node (ref "MANUAL_LOG") (pin "1") (pinfunction "S_1") (pintype "passive"))
      (node (ref "RTC_DS3234") (pin "5") (pinfunction "INT/SQW_5") (pintype "bidirectional"))
      (node (ref "RTC_INT_PU") (pin "1") (pinfunction "1_1") (pintype "passive"))
    )
    (net (code "25") (name "/D3-INT1") (class "Default")
      (node (ref "IC3") (pin "7") (pinfunction "(OC3C/INT5)PE5_7") (pintype "bidirectional"))
      (node (ref "U$11") (pin "1") (pinfunction "1_1") (pintype "passive"))
    )
    (net (code "26") (name "/D4") (class "Default")
      (node (ref "IC3") (pin "1") (pinfunction "(OC0B)PG5_1") (pintype "bidirectional"))
      (node (ref "U$9") (pin "D4") (pinfunction "D4_D4") (pintype "bidirectional"))
    )
    (net (code "27") (name "/D5") (class "Default")
      (node (ref "IC3") (pin "5") (pinfunction "(OC3A/AIN1)PE3_5") (pintype "bidirectional"))
      (node (ref "U$7") (pin "D5") (pinfunction "D5_D5") (pintype "bidirectional"))
      (node (ref "U$9") (pin "D5") (pinfunction "D5_D5") (pintype "bidirectional"))
    )
    (net (code "28") (name "/D6") (class "Default")
      (node (ref "IC3") (pin "15") (pinfunction "PH3(OC4A)_15") (pintype "bidirectional"))
      (node (ref "U$7") (pin "D6") (pinfunction "D6_D6") (pintype "bidirectional"))
      (node (ref "U$9") (pin "D6") (pinfunction "D6_D6") (pintype "bidirectional"))
    )
    (net (code "29") (name "/D7") (class "Default")
      (node (ref "IC3") (pin "16") (pinfunction "PH4(OC4B)_16") (pintype "bidirectional"))
      (node (ref "U$9") (pin "D7") (pinfunction "D7_D7") (pintype "bidirectional"))
    )
    (net (code "30") (name "/D8") (class "Default")
      (node (ref "IC3") (pin "17") (pinfunction "PH5(OC4C)_17") (pintype "bidirectional"))
      (node (ref "U$7") (pin "D8") (pinfunction "D8_D8") (pintype "bidirectional"))
      (node (ref "U$9") (pin "D8") (pinfunction "D8_D8") (pintype "bidirectional"))
    )
    (net (code "31") (name "/D9") (class "Default")
      (node (ref "IC3") (pin "18") (pinfunction "PH6(OC2B)_18") (pintype "bidirectional"))
      (node (ref "U$7") (pin "D9") (pinfunction "D9_D9") (pintype "bidirectional"))
      (node (ref "U$9") (pin "D9") (pinfunction "D9_D9") (pintype "bidirectional"))
    )
    (net (code "32") (name "/D10") (class "Default")
      (node (ref "IC3") (pin "23") (pinfunction "(OC2A/PCINT4)PB4_23") (pintype "bidirectional"))
      (node (ref "U$14") (pin "9") (pinfunction "9_9") (pintype "passive"))
    )
    (net (code "33") (name "/D11") (class "Default")
      (node (ref "IC3") (pin "24") (pinfunction "(OC1A/PCINT5)PB5_24") (pintype "bidirectional"))
      (node (ref "U$14") (pin "10") (pinfunction "10_10") (pintype "passive"))
    )
    (net (code "34") (name "/D12") (class "Default")
      (node (ref "IC3") (pin "25") (pinfunction "(OC1B/PCINT6)PB6_25") (pintype "bidirectional"))
      (node (ref "U$14") (pin "11") (pinfunction "11_11") (pintype "passive"))
    )
    (net (code "35") (name "/D13") (class "Default")
      (node (ref "IC3") (pin "26") (pinfunction "(OC0A/OC1C/PCINT7)PB7_26") (pintype "bidirectional"))
      (node (ref "U$14") (pin "12") (pinfunction "12_12") (pintype "passive"))
    )
    (net (code "36") (name "/D14-TX3") (class "Default")
      (node (ref "IC3") (pin "64") (pinfunction "PJ1(TXD3/PCINT10)_64") (pintype "bidirectional"))
      (node (ref "U$11") (pin "5") (pinfunction "5_5") (pintype "passive"))
      (node (ref "U$7") (pin "TX") (pinfunction "TX_TX") (pintype "bidirectional"))
    )
    (net (code "37") (name "/D15-RX3") (class "Default")
      (node (ref "IC3") (pin "63") (pinfunction "PJ0(RXD3/PCINT9)_63") (pintype "bidirectional"))
      (node (ref "U$11") (pin "4") (pinfunction "4_4") (pintype "passive"))
      (node (ref "U$7") (pin "RX") (pinfunction "RX_RX") (pintype "bidirectional"))
    )
    (net (code "38") (name "/D16-TX2") (class "Default")
      (node (ref "IC3") (pin "13") (pinfunction "PH1(TXD2)_13") (pintype "bidirectional"))
      (node (ref "U$14") (pin "4") (pinfunction "4_4") (pintype "passive"))
    )
    (net (code "39") (name "/D17-RX2") (class "Default")
      (node (ref "IC3") (pin "12") (pinfunction "PH0(RXD2)_12") (pintype "bidirectional"))
      (node (ref "U$14") (pin "3") (pinfunction "3_3") (pintype "passive"))
    )
    (net (code "40") (name "/D18-TX1-INT5") (class "Default")
      (node (ref "IC3") (pin "46") (pinfunction "(TXD1/INT3)PD3_46") (pintype "bidirectional"))
      (node (ref "IC4") (pin "3") (pinfunction "I_3") (pintype "input"))
      (node (ref "U$7") (pin "D3") (pinfunction "INT1_D3") (pintype "bidirectional"))
      (node (ref "U$9") (pin "D3") (pinfunction "INT1_D3") (pintype "bidirectional"))
    )
    (net (code "41") (name "/D18-TX1-INT5-3V3") (class "Default")
      (node (ref "IC4") (pin "2") (pinfunction "O_2") (pintype "output"))
      (node (ref "U$12") (pin "11") (pinfunction "11_11") (pintype "passive"))
    )
    (net (code "42") (name "/D19-RX1-INT4") (class "Default")
      (node (ref "IC3") (pin "45") (pinfunction "(RXD1/INT2)PD2_45") (pintype "bidirectional"))
      (node (ref "IC4") (pin "5") (pinfunction "I_5") (pintype "input"))
      (node (ref "U$7") (pin "D2") (pinfunction "INT0_D2") (pintype "bidirectional"))
      (node (ref "U$9") (pin "D2") (pinfunction "INT0_D2") (pintype "bidirectional"))
    )
    (net (code "43") (name "/D19-RX1-INT4-3V3") (class "Default")
      (node (ref "IC4") (pin "4") (pinfunction "O_4") (pintype "output"))
      (node (ref "U$12") (pin "12") (pinfunction "12_12") (pintype "passive"))
    )
    (net (code "44") (name "/D20-SDA-INT3") (class "Default")
      (node (ref "IC2") (pin "9") (pinfunction "I_9") (pintype "input"))
      (node (ref "IC3") (pin "44") (pinfunction "(SDA/INT1)PD1_44") (pintype "bidirectional"))
      (node (ref "SDA_PU") (pin "1") (pinfunction "1_1") (pintype "passive"))
      (node (ref "U$11") (pin "2") (pinfunction "2_2") (pintype "passive"))
      (node (ref "U$7") (pin "A4") (pinfunction "SDA_A4") (pintype "bidirectional"))
      (node (ref "U$7") (pin "SDA") (pinfunction "SDA1_SDA") (pintype "bidirectional"))
      (node (ref "U$9") (pin "A4") (pinfunction "SDA_A4") (pintype "bidirectional"))
      (node (ref "U$9") (pin "SDA") (pinfunction "SDA1_SDA") (pintype "bidirectional"))
    )
    (net (code "45") (name "/D20-SDA-INT3-3V3") (class "Default")
      (node (ref "IC2") (pin "10") (pinfunction "O_10") (pintype "output"))
      (node (ref "U$12") (pin "6") (pinfunction "6_6") (pintype "passive"))
    )
    (net (code "46") (name "/D21-SCL-INT2") (class "Default")
      (node (ref "IC2") (pin "11") (pinfunction "I_11") (pintype "input"))
      (node (ref "IC3") (pin "43") (pinfunction "(SCL/INT0)PD0_43") (pintype "bidirectional"))
      (node (ref "SCL_PU") (pin "1") (pinfunction "1_1") (pintype "passive"))
      (node (ref "U$11") (pin "3") (pinfunction "3_3") (pintype "passive"))
      (node (ref "U$7") (pin "A5") (pinfunction "SCL_A5") (pintype "bidirectional"))
      (node (ref "U$7") (pin "SCL") (pinfunction "SCL1_SCL") (pintype "bidirectional"))
      (node (ref "U$9") (pin "A5") (pinfunction "SCL_A5") (pintype "bidirectional"))
      (node (ref "U$9") (pin "SCL") (pinfunction "SCL1_SCL") (pintype "bidirectional"))
    )
    (net (code "47") (name "/D21-SCL-INT2-3V3") (class "Default")
      (node (ref "IC2") (pin "12") (pinfunction "O_12") (pintype "output"))
      (node (ref "U$12") (pin "5") (pinfunction "5_5") (pintype "passive"))
    )
    (net (code "48") (name "/D22") (class "Default")
      (node (ref "IC3") (pin "78") (pinfunction "(AD0)PA0_78") (pintype "bidirectional"))
      (node (ref "JP7") (pin "1") (pinfunction "1_1") (pintype "passive"))
    )
    (net (code "49") (name "/D23") (class "Default")
      (node (ref "IC3") (pin "77") (pinfunction "(AD1)PA1_77") (pintype "bidirectional"))
      (node (ref "JP7") (pin "3") (pinfunction "3_3") (pintype "passive"))
    )
    (net (code "50") (name "/D24") (class "Default")
      (node (ref "IC3") (pin "76") (pinfunction "(AD2)PA2_76") (pintype "bidirectional"))
      (node (ref "JP7") (pin "5") (pinfunction "5_5") (pintype "passive"))
    )
    (net (code "51") (name "/D25") (class "Default")
      (node (ref "IC3") (pin "75") (pinfunction "(AD3)PA3_75") (pintype "bidirectional"))
      (node (ref "JP7") (pin "7") (pinfunction "7_7") (pintype "passive"))
    )
    (net (code "52") (name "/D26") (class "Default")
      (node (ref "IC3") (pin "74") (pinfunction "(AD4)PA4_74") (pintype "bidirectional"))
      (node (ref "JP7") (pin "9") (pinfunction "9_9") (pintype "passive"))
    )
    (net (code "53") (name "/D27") (class "Default")
      (node (ref "IC3") (pin "73") (pinfunction "(AD5)PA5_73") (pintype "bidirectional"))
      (node (ref "JP7") (pin "10") (pinfunction "10_10") (pintype "passive"))
    )
    (net (code "54") (name "/D28") (class "Default")
      (node (ref "IC3") (pin "72") (pinfunction "(AD6)PA6_72") (pintype "bidirectional"))
      (node (ref "JP7") (pin "8") (pinfunction "8_8") (pintype "passive"))
    )
    (net (code "55") (name "/D29") (class "Default")
      (node (ref "IC3") (pin "71") (pinfunction "(AD7)PA7_71") (pintype "bidirectional"))
      (node (ref "JP7") (pin "6") (pinfunction "6_6") (pintype "passive"))
    )
    (net (code "56") (name "/D30") (class "Default")
      (node (ref "IC3") (pin "60") (pinfunction "(A15)PC7_60") (pintype "bidirectional"))
      (node (ref "JP7") (pin "4") (pinfunction "4_4") (pintype "passive"))
    )
    (net (code "57") (name "/D31") (class "Default")
      (node (ref "IC3") (pin "59") (pinfunction "(A14)PC6_59") (pintype "bidirectional"))
    )
    (net (code "58") (name "/D32") (class "Default")
      (node (ref "IC3") (pin "58") (pinfunction "(A13)PC5_58") (pintype "bidirectional"))
    )
    (net (code "59") (name "/D33") (class "Default")
      (node (ref "IC3") (pin "57") (pinfunction "(A12)PC4_57") (pintype "bidirectional"))
      (node (ref "IC4") (pin "7") (pinfunction "I_7") (pintype "input"))
    )
    (net (code "60") (name "/D33-3V3") (class "Default")
      (node (ref "IC4") (pin "6") (pinfunction "O_6") (pintype "output"))
      (node (ref "U$12") (pin "13") (pinfunction "13_13") (pintype "passive"))
    )
    (net (code "61") (name "/D34") (class "Default")
      (node (ref "IC3") (pin "56") (pinfunction "(A11)PC3_56") (pintype "bidirectional"))
      (node (ref "IC4") (pin "9") (pinfunction "I_9") (pintype "input"))
    )
    (net (code "62") (name "/D34-3V3") (class "Default")
      (node (ref "IC4") (pin "10") (pinfunction "O_10") (pintype "output"))
      (node (ref "U$12") (pin "4") (pinfunction "4_4") (pintype "passive"))
    )
    (net (code "63") (name "/D35") (class "Default")
      (node (ref "IC3") (pin "55") (pinfunction "(A10)PC2_55") (pintype "bidirectional"))
      (node (ref "IC4") (pin "11") (pinfunction "I_11") (pintype "input"))
    )
    (net (code "64") (name "/D35-3V3") (class "Default")
      (node (ref "IC4") (pin "12") (pinfunction "O_12") (pintype "output"))
      (node (ref "U$12") (pin "3") (pinfunction "3_3") (pintype "passive"))
    )
    (net (code "65") (name "/D36") (class "Default")
      (node (ref "IC3") (pin "54") (pinfunction "(A9)PC1_54") (pintype "bidirectional"))
      (node (ref "IC4") (pin "14") (pinfunction "I_14") (pintype "input"))
    )
    (net (code "66") (name "/D36-3V3") (class "Default")
      (node (ref "IC4") (pin "15") (pinfunction "O_15") (pintype "output"))
      (node (ref "U$12") (pin "2") (pinfunction "2_2") (pintype "passive"))
    )
    (net (code "67") (name "/D37") (class "Default")
      (node (ref "IC2") (pin "14") (pinfunction "I_14") (pintype "input"))
      (node (ref "IC3") (pin "53") (pinfunction "(A8)PC0_53") (pintype "bidirectional"))
    )
    (net (code "68") (name "/D37-3V3") (class "Default")
      (node (ref "IC2") (pin "15") (pinfunction "O_15") (pintype "output"))
      (node (ref "U$12") (pin "1") (pinfunction "1_1") (pintype "passive"))
    )
    (net (code "69") (name "/D38-SHIELD4") (class "Default")
      (node (ref "IC3") (pin "50") (pinfunction "(T0)PD7_50") (pintype "bidirectional"))
      (node (ref "U$7") (pin "D4") (pinfunction "D4_D4") (pintype "bidirectional"))
    )
    (net (code "70") (name "/D39-SWVCC") (class "Default")
      (node (ref "IC3") (pin "70") (pinfunction "(ALE)PG2_70") (pintype "bidirectional"))
      (node (ref "M1") (pin "5") (pinfunction "ON/OFF_5") (pintype "bidirectional"))
      (node (ref "M2") (pin "5") (pinfunction "ON/OFF_5") (pintype "bidirectional"))
      (node (ref "SW") (pin "5") (pinfunction "ON/OFF_5") (pintype "bidirectional"))
    )
    (net (code "71") (name "/D40-SHIELD0_CS") (class "Default")
      (node (ref "IC3") (pin "52") (pinfunction "(RD)PG1_52") (pintype "bidirectional"))
      (node (ref "U$9") (pin "D10") (pinfunction "CS_D10") (pintype "bidirectional"))
    )
    (net (code "72") (name "/D41-SHIELD1_CS") (class "Default")
      (node (ref "IC3") (pin "51") (pinfunction "(WR)PG0_51") (pintype "bidirectional"))
      (node (ref "U$7") (pin "D10") (pinfunction "CS_D10") (pintype "bidirectional"))
    )
    (net (code "73") (name "/D42-SENSE_3V3_SWITCH") (class "Default")
      (node (ref "IC3") (pin "42") (pinfunction "PL7_42") (pintype "bidirectional"))
      (node (ref "LD0_SENSE") (pin "3") (pinfunction "EN_3") (pintype "bidirectional"))
    )
    (net (code "74") (name "/D43_MANUAL_LOG") (class "Default")
      (node (ref "IC3") (pin "41") (pinfunction "PL6_41") (pintype "bidirectional"))
      (node (ref "MANUAL_LOG") (pin "3") (pinfunction "S_3") (pintype "passive"))
    )
    (net (code "75") (name "/D44") (class "Default")
      (node (ref "IC3") (pin "40") (pinfunction "PL5(OC5C)_40") (pintype "bidirectional"))
      (node (ref "U$11") (pin "15") (pinfunction "15_15") (pintype "passive"))
    )
    (net (code "76") (name "/D45") (class "Default")
      (node (ref "IC3") (pin "39") (pinfunction "PL4(OC5B)_39") (pintype "bidirectional"))
      (node (ref "U$11") (pin "16") (pinfunction "16_16") (pintype "passive"))
    )
    (net (code "77") (name "/D46-SHIELD7") (class "Default")
      (node (ref "IC3") (pin "38") (pinfunction "PL3(OC5A)_38") (pintype "bidirectional"))
      (node (ref "U$7") (pin "D7") (pinfunction "D7_D7") (pintype "bidirectional"))
    )
    (net (code "78") (name "/D47_CS_RTC") (class "Default")
      (node (ref "IC3") (pin "37") (pinfunction "PL2(T5)_37") (pintype "bidirectional"))
      (node (ref "RTC_DS3234") (pin "1") (pinfunction "CS_1") (pintype "bidirectional"))
    )
    (net (code "79") (name "/D48-SD_3V3_SWITCH") (class "Default")
      (node (ref "IC3") (pin "36") (pinfunction "PL1(ICP5)_36") (pintype "bidirectional"))
      (node (ref "LD0_SD") (pin "3") (pinfunction "EN_3") (pintype "bidirectional"))
    )
    (net (code "80") (name "/D49-LED") (class "Default")
      (node (ref "IC3") (pin "35") (pinfunction "PL0(ICP4)_35") (pintype "bidirectional"))
      (node (ref "R_LED") (pin "1") (pinfunction "1_1") (pintype "passive"))
    )
    (net (code "81") (name "/D50-MISO") (class "Default")
      (node (ref "IC2") (pin "3") (pinfunction "I_3") (pintype "input"))
      (node (ref "IC3") (pin "22") (pinfunction "(MISO/PCINT3)PB3_22") (pintype "bidirectional"))
      (node (ref "ISP") (pin "1") (pinfunction "MISO_1") (pintype "input"))
      (node (ref "RTC_DS3234") (pin "19") (pinfunction "DOUT_19") (pintype "bidirectional"))
      (node (ref "SD") (pin "7") (pinfunction "DATA_OUT_7") (pintype "output"))
      (node (ref "U$14") (pin "13") (pinfunction "13_13") (pintype "passive"))
      (node (ref "U$7") (pin "D12") (pinfunction "MISO_D12") (pintype "bidirectional"))
      (node (ref "U$9") (pin "D12") (pinfunction "MISO_D12") (pintype "bidirectional"))
    )
    (net (code "82") (name "/D50-MISO-3V3") (class "Default")
      (node (ref "IC2") (pin "2") (pinfunction "O_2") (pintype "output"))
      (node (ref "U$12") (pin "9") (pinfunction "9_9") (pintype "passive"))
    )
    (net (code "83") (name "/D51-MOSI") (class "Default")
      (node (ref "IC2") (pin "5") (pinfunction "I_5") (pintype "input"))
      (node (ref "IC3") (pin "21") (pinfunction "(MOSI/PCINT2)PB2_21") (pintype "bidirectional"))
      (node (ref "ISP") (pin "4") (pinfunction "MOSI_4") (pintype "output"))
      (node (ref "LSHIFT") (pin "5") (pinfunction "I_5") (pintype "input"))
      (node (ref "RTC_DS3234") (pin "17") (pinfunction "DIN_17") (pintype "bidirectional"))
      (node (ref "U$14") (pin "14") (pinfunction "14_14") (pintype "passive"))
      (node (ref "U$7") (pin "D11") (pinfunction "MOSI_D11") (pintype "bidirectional"))
      (node (ref "U$9") (pin "D11") (pinfunction "MOSI_D11") (pintype "bidirectional"))
    )
    (net (code "84") (name "/D51-MOSI-3V3") (class "Default")
      (node (ref "IC2") (pin "4") (pinfunction "O_4") (pintype "output"))
      (node (ref "U$12") (pin "8") (pinfunction "8_8") (pintype "passive"))
    )
    (net (code "85") (name "/D52-SCLK") (class "Default")
      (node (ref "IC2") (pin "7") (pinfunction "I_7") (pintype "input"))
      (node (ref "IC3") (pin "20") (pinfunction "(SCK/PCINT1)PB1_20") (pintype "bidirectional"))
      (node (ref "ISP") (pin "3") (pinfunction "SCK_3") (pintype "output"))
      (node (ref "LSHIFT") (pin "3") (pinfunction "I_3") (pintype "input"))
      (node (ref "RTC_DS3234") (pin "18") (pinfunction "SCLK_18") (pintype "bidirectional"))
      (node (ref "RTC_DS3234") (pin "20") (pinfunction "SCLK_20") (pintype "bidirectional"))
      (node (ref "U$14") (pin "15") (pinfunction "15_15") (pintype "passive"))
      (node (ref "U$7") (pin "D13") (pinfunction "SCK_D13") (pintype "bidirectional"))
      (node (ref "U$9") (pin "D13") (pinfunction "SCK_D13") (pintype "bidirectional"))
    )
    (net (code "86") (name "/D52-SCLK-3V3") (class "Default")
      (node (ref "IC2") (pin "6") (pinfunction "O_6") (pintype "output"))
      (node (ref "U$12") (pin "7") (pinfunction "7_7") (pintype "passive"))
    )
    (net (code "87") (name "/D53-CS_SD") (class "Default")
      (node (ref "IC3") (pin "19") (pinfunction "(SS/PCINT0)PB0_19") (pintype "bidirectional"))
      (node (ref "LSHIFT") (pin "7") (pinfunction "I_7") (pintype "input"))
    )
    (net (code "88") (name "/DTR") (class "Default")
      (node (ref "C_RESET") (pin "1") (pinfunction "1_1") (pintype "passive"))
      (node (ref "U1") (pin "2") (pinfunction "DTR_2") (pintype "bidirectional"))
    )
    (net (code "89") (name "/RESET") (class "Default")
      (node (ref "C1") (pin "1") (pinfunction "1_1") (pintype "passive"))
      (node (ref "C_RESET") (pin "2") (pinfunction "2_2") (pintype "passive"))
      (node (ref "D3") (pin "A") (pinfunction "A_A") (pintype "passive"))
      (node (ref "IC3") (pin "30") (pinfunction "RESET_30") (pintype "input"))
      (node (ref "ISP") (pin "5") (pinfunction "RST_5") (pintype "output"))
      (node (ref "R_RESET") (pin "1") (pinfunction "1_1") (pintype "passive"))
      (node (ref "S2") (pin "3") (pinfunction "3_3") (pintype "passive"))
      (node (ref "S2") (pin "4") (pinfunction "4_4") (pintype "passive"))
      (node (ref "U$7") (pin "RES") (pinfunction "/RESET_RES") (pintype "bidirectional"))
      (node (ref "U$9") (pin "RES") (pinfunction "/RESET_RES") (pintype "bidirectional"))
    )
    (net (code "90") (name "/SD_CLK") (class "Default")
      (node (ref "LSHIFT") (pin "2") (pinfunction "O_2") (pintype "output"))
      (node (ref "SD") (pin "5") (pinfunction "SCLK_5") (pintype "input"))
    )
    (net (code "91") (name "/SD_CS") (class "Default")
      (node (ref "LSHIFT") (pin "6") (pinfunction "O_6") (pintype "output"))
      (node (ref "SD") (pin "1") (pinfunction "CS_1") (pintype "input"))
    )
    (net (code "92") (name "/SD_DI") (class "Default")
      (node (ref "LSHIFT") (pin "4") (pinfunction "O_4") (pintype "output"))
      (node (ref "SD") (pin "2") (pinfunction "DATA_IN_2") (pintype "input"))
    )
    (net (code "93") (name "/VCC_SW") (class "Default")
      (node (ref "SW") (pin "2") (pinfunction "VOUT,C1_PIN2_2") (pintype "bidirectional"))
      (node (ref "U$11") (pin "10") (pinfunction "10_10") (pintype "passive"))
      (node (ref "U$11") (pin "11") (pinfunction "11_11") (pintype "passive"))
      (node (ref "U$14") (pin "8") (pinfunction "8_8") (pintype "passive"))
    )
    (net (code "94") (name "/VCC_SW_SHIELD1") (class "Default")
      (node (ref "M1") (pin "2") (pinfunction "VOUT,C1_PIN2_2") (pintype "bidirectional"))
      (node (ref "U$7") (pin "IOREF") (pinfunction "IOREF_IOREF") (pintype "bidirectional"))
      (node (ref "U$9") (pin "5V") (pinfunction "VCC_5V") (pintype "power_in"))
      (node (ref "U$9") (pin "IOREF") (pinfunction "IOREF_IOREF") (pintype "bidirectional"))
      (node (ref "U$9") (pin "VIN") (pinfunction "VIN_VIN") (pintype "power_in"))
    )
    (net (code "95") (name "/VCC_SW_SHIELD2") (class "Default")
      (node (ref "M2") (pin "2") (pinfunction "VOUT,C1_PIN2_2") (pintype "bidirectional"))
      (node (ref "U$7") (pin "5V") (pinfunction "VCC_5V") (pintype "power_in"))
      (node (ref "U$7") (pin "VIN") (pinfunction "VIN_VIN") (pintype "power_in"))
    )
    (net (code "96") (name "/XTAL1") (class "Default")
      (node (ref "CX1") (pin "2") (pinfunction "2_2") (pintype "passive"))
      (node (ref "IC3") (pin "34") (pinfunction "XTAL1_34") (pintype "input"))
      (node (ref "U$8") (pin "IO1") (pinfunction "IO1_IO1") (pintype "bidirectional"))
    )
    (net (code "97") (name "/XTAL2") (class "Default")
      (node (ref "CX0") (pin "2") (pinfunction "2_2") (pintype "passive"))
      (node (ref "IC3") (pin "33") (pinfunction "XTAL2_33") (pintype "output"))
      (node (ref "U$8") (pin "IO2") (pinfunction "IO2_IO2") (pintype "bidirectional"))
    )
    (net (code "98") (name "GND") (class "Default")
      (node (ref "C1") (pin "2") (pinfunction "2_2") (pintype "passive"))
      (node (ref "C11") (pin "1") (pinfunction "1_1") (pintype "passive"))
      (node (ref "C3") (pin "2") (pinfunction "2_2") (pintype "passive"))
      (node (ref "C4") (pin "2") (pinfunction "2_2") (pintype "passive"))
      (node (ref "C5") (pin "2") (pinfunction "2_2") (pintype "passive"))
      (node (ref "C6") (pin "2") (pinfunction "2_2") (pintype "passive"))
      (node (ref "CBB") (pin "C") (pinfunction "-_C") (pintype "passive"))
      (node (ref "CLOCK_BATT") (pin "-") (pinfunction "-_-") (pintype "passive"))
      (node (ref "COUT") (pin "2") (pinfunction "2_2") (pintype "passive"))
      (node (ref "CX0") (pin "1") (pinfunction "1_1") (pintype "passive"))
      (node (ref "CX1") (pin "1") (pinfunction "1_1") (pintype "passive"))
      (node (ref "C_LDO_SD") (pin "1") (pinfunction "1_1") (pintype "passive"))
      (node (ref "C_LDO_SENSE") (pin "1") (pinfunction "1_1") (pintype "passive"))
      (node (ref "DECOUP") (pin "2") (pinfunction "2_2") (pintype "passive"))
      (node (ref "H1") (pin "1") (pinfunction "1_1") (pintype "passive"))
      (node (ref "IC1") (pin "2") (pinfunction "GND_2") (pintype "passive"))
      (node (ref "IC1") (pin "3") (pinfunction "CTL_3") (pintype "input"))
      (node (ref "IC2") (pin "8") (pinfunction "VSS_8") (pintype "power_in"))
      (node (ref "IC3") (pin "11") (pinfunction "GND_11") (pintype "power_in"))
      (node (ref "IC3") (pin "32") (pinfunction "GND1_32") (pintype "power_in"))
      (node (ref "IC3") (pin "62") (pinfunction "GND2_62") (pintype "power_in"))
      (node (ref "IC3") (pin "81") (pinfunction "GND3_81") (pintype "power_in"))
      (node (ref "IC3") (pin "99") (pinfunction "AGND_99") (pintype "power_in"))
      (node (ref "IC4") (pin "8") (pinfunction "VSS_8") (pintype "power_in"))
      (node (ref "ISP") (pin "6") (pinfunction "GND_6") (pintype "power_in"))
      (node (ref "J1") (pin "GND") (pinfunction "GND_GND") (pintype "bidirectional"))
      (node (ref "J1") (pin "GNDBREAK") (pinfunction "GNDBREAK_GNDBREAK") (pintype "bidirectional"))
      (node (ref "JP5") (pin "GND") (pinfunction "GND_GND") (pintype "bidirectional"))
      (node (ref "JP7") (pin "2") (pinfunction "2_2") (pintype "passive"))
      (node (ref "LD0_SD") (pin "2") (pinfunction "GND_2") (pintype "bidirectional"))
      (node (ref "LD0_SENSE") (pin "2") (pinfunction "GND_2") (pintype "bidirectional"))
      (node (ref "LED") (pin "K") (pinfunction "C_K") (pintype "passive"))
      (node (ref "LSHIFT") (pin "11") (pinfunction "I_11") (pintype "input"))
      (node (ref "LSHIFT") (pin "14") (pinfunction "I_14") (pintype "input"))
      (node (ref "LSHIFT") (pin "8") (pinfunction "VSS_8") (pintype "power_in"))
      (node (ref "LSHIFT") (pin "9") (pinfunction "I_9") (pintype "input"))
      (node (ref "M0R1") (pin "1") (pinfunction "1_1") (pintype "passive"))
      (node (ref "M1R2") (pin "1") (pinfunction "1_1") (pintype "passive"))
      (node (ref "M2R2") (pin "1") (pinfunction "1_1") (pintype "passive"))
      (node (ref "MANUAL_LOG") (pin "2") (pinfunction "P_2") (pintype "passive"))
      (node (ref "MANUAL_LOG") (pin "4") (pinfunction "P_4") (pintype "passive"))
      (node (ref "RTC_DS3234") (pin "10") (pinfunction "GND_10") (pintype "bidirectional"))
      (node (ref "RTC_DS3234") (pin "11") (pinfunction "GND_11") (pintype "bidirectional"))
      (node (ref "RTC_DS3234") (pin "12") (pinfunction "GND_12") (pintype "bidirectional"))
      (node (ref "RTC_DS3234") (pin "13") (pinfunction "GND_13") (pintype "bidirectional"))
      (node (ref "RTC_DS3234") (pin "14") (pinfunction "GND_14") (pintype "bidirectional"))
      (node (ref "RTC_DS3234") (pin "15") (pinfunction "GND_15") (pintype "bidirectional"))
      (node (ref "RTC_DS3234") (pin "2") (pinfunction "GND_2") (pintype "bidirectional"))
      (node (ref "RTC_DS3234") (pin "7") (pinfunction "GND_7") (pintype "bidirectional"))
      (node (ref "RTC_DS3234") (pin "8") (pinfunction "GND_8") (pintype "bidirectional"))
      (node (ref "RTC_DS3234") (pin "9") (pinfunction "GND_9") (pintype "bidirectional"))
      (node (ref "R_REF_A0") (pin "1") (pinfunction "1_1") (pintype "passive"))
      (node (ref "R_REF_A1") (pin "1") (pinfunction "1_1") (pintype "passive"))
      (node (ref "R_REF_A10") (pin "1") (pinfunction "1_1") (pintype "passive"))
      (node (ref "R_REF_A11") (pin "1") (pinfunction "1_1") (pintype "passive"))
      (node (ref "R_REF_A12") (pin "1") (pinfunction "1_1") (pintype "passive"))
      (node (ref "R_REF_A13") (pin "1") (pinfunction "1_1") (pintype "passive"))
      (node (ref "R_REF_A14") (pin "1") (pinfunction "1_1") (pintype "passive"))
      (node (ref "R_REF_A2") (pin "1") (pinfunction "1_1") (pintype "passive"))
      (node (ref "R_REF_A3") (pin "1") (pinfunction "1_1") (pintype "passive"))
      (node (ref "R_REF_A4") (pin "1") (pinfunction "1_1") (pintype "passive"))
      (node (ref "R_REF_A5") (pin "1") (pinfunction "1_1") (pintype "passive"))
      (node (ref "R_REF_A6") (pin "1") (pinfunction "1_1") (pintype "passive"))
      (node (ref "R_REF_A7") (pin "1") (pinfunction "1_1") (pintype "passive"))
      (node (ref "R_REF_A8") (pin "1") (pinfunction "1_1") (pintype "passive"))
      (node (ref "R_REF_A9") (pin "1") (pinfunction "1_1") (pintype "passive"))
      (node (ref "S2") (pin "1") (pinfunction "1_1") (pintype "passive"))
      (node (ref "S2") (pin "2") (pinfunction "2_2") (pintype "passive"))
      (node (ref "SD") (pin "3") (pinfunction "VSS1_3") (pintype "power_in"))
      (node (ref "SD") (pin "6") (pinfunction "VSS2_6") (pintype "power_in"))
      (node (ref "SD") (pin "GP") (pinfunction "GND_GP") (pintype "power_in"))
      (node (ref "SD") (pin "GP3") (pinfunction "COMMON_SW_GP3") (pintype "passive"))
      (node (ref "U$11") (pin "12") (pinfunction "12_12") (pintype "passive"))
      (node (ref "U$11") (pin "13") (pinfunction "13_13") (pintype "passive"))
      (node (ref "U$11") (pin "14") (pinfunction "14_14") (pintype "passive"))
      (node (ref "U$11") (pin "8") (pinfunction "8_8") (pintype "passive"))
      (node (ref "U$11") (pin "9") (pinfunction "9_9") (pintype "passive"))
      (node (ref "U$12") (pin "10") (pinfunction "10_10") (pintype "passive"))
      (node (ref "U$14") (pin "16") (pinfunction "16_16") (pintype "passive"))
      (node (ref "U$14") (pin "6") (pinfunction "6_6") (pintype "passive"))
      (node (ref "U$14") (pin "7") (pinfunction "7_7") (pintype "passive"))
      (node (ref "U$7") (pin "GND@0") (pinfunction "GND_GND@0") (pintype "power_in"))
      (node (ref "U$7") (pin "GND@1") (pinfunction "GND1_GND@1") (pintype "power_in"))
      (node (ref "U$7") (pin "GND@2") (pinfunction "GND2_GND@2") (pintype "power_in"))
      (node (ref "U$8") (pin "GND") (pinfunction "GND_GND") (pintype "power_in"))
      (node (ref "U$9") (pin "GND@0") (pinfunction "GND_GND@0") (pintype "power_in"))
      (node (ref "U$9") (pin "GND@1") (pinfunction "GND1_GND@1") (pintype "power_in"))
      (node (ref "U$9") (pin "GND@2") (pinfunction "GND2_GND@2") (pintype "power_in"))
      (node (ref "U1") (pin "11") (pinfunction "CTS_11") (pintype "bidirectional"))
      (node (ref "U1") (pin "18") (pinfunction "GND2_18") (pintype "power_in"))
      (node (ref "U1") (pin "21") (pinfunction "GND3_21") (pintype "power_in"))
      (node (ref "U1") (pin "25") (pinfunction "AGND_25") (pintype "power_in"))
      (node (ref "U1") (pin "26") (pinfunction "TEST_26") (pintype "input"))
      (node (ref "U1") (pin "7") (pinfunction "GND1_7") (pintype "power_in"))
      (node (ref "USBD0") (pin "2") (pinfunction "2_2") (pintype "passive"))
      (node (ref "USBD1") (pin "C") (pinfunction "-_C") (pintype "passive"))
      (node (ref "VCC_VDIV_2") (pin "1") (pinfunction "1_1") (pintype "passive"))
    )
    (net (code "99") (name "Net-(IC1-GATE)") (class "Default")
      (node (ref "IC1") (pin "5") (pinfunction "GATE_5") (pintype "output"))
      (node (ref "Q1") (pin "1") (pinfunction "G_1") (pintype "passive"))
    )
    (net (code "100") (name "Net-(IC1-STAT)") (class "Default")
      (node (ref "IC1") (pin "4") (pinfunction "STAT_4") (pintype "open_collector"))
      (node (ref "Q2") (pin "1") (pinfunction "G_1") (pintype "passive"))
      (node (ref "RSTAT") (pin "1") (pinfunction "1_1") (pintype "passive"))
    )
    (net (code "101") (name "Net-(LED-PadA)") (class "Default")
      (node (ref "LED") (pin "A") (pinfunction "A_A") (pintype "passive"))
      (node (ref "R_LED") (pin "2") (pinfunction "2_2") (pintype "passive"))
    )
    (net (code "102") (name "Net-(M1-R1,C1)") (class "Default")
      (node (ref "M1") (pin "6") (pinfunction "R1,C1_6") (pintype "bidirectional"))
      (node (ref "M1C1") (pin "1") (pinfunction "1_1") (pintype "passive"))
      (node (ref "M1R1") (pin "2") (pinfunction "2_2") (pintype "passive"))
    )
    (net (code "103") (name "Net-(M1-R2)") (class "Default")
      (node (ref "M1") (pin "1") (pinfunction "R2_1") (pintype "bidirectional"))
      (node (ref "M1R2") (pin "2") (pinfunction "2_2") (pintype "passive"))
    )
    (net (code "104") (name "Net-(M1-VOUT,C1)") (class "Default")
      (node (ref "M1") (pin "3") (pinfunction "VOUT,C1_3") (pintype "bidirectional"))
      (node (ref "M1C1") (pin "2") (pinfunction "2_2") (pintype "passive"))
    )
    (net (code "105") (name "Net-(M2-R1,C1)") (class "Default")
      (node (ref "M2") (pin "6") (pinfunction "R1,C1_6") (pintype "bidirectional"))
      (node (ref "M2C1") (pin "1") (pinfunction "1_1") (pintype "passive"))
      (node (ref "M2R1") (pin "2") (pinfunction "2_2") (pintype "passive"))
    )
    (net (code "106") (name "Net-(M2-R2)") (class "Default")
      (node (ref "M2") (pin "1") (pinfunction "R2_1") (pintype "bidirectional"))
      (node (ref "M2R2") (pin "2") (pinfunction "2_2") (pintype "passive"))
    )
    (net (code "107") (name "Net-(M2-VOUT,C1)") (class "Default")
      (node (ref "M2") (pin "3") (pinfunction "VOUT,C1_3") (pintype "bidirectional"))
      (node (ref "M2C1") (pin "2") (pinfunction "2_2") (pintype "passive"))
    )
    (net (code "108") (name "Net-(RTC_DS3234-RST)") (class "Default")
      (node (ref "RTC_DS3234") (pin "6") (pinfunction "RST_6") (pintype "bidirectional"))
      (node (ref "RTC_RST_PU") (pin "1") (pinfunction "1_1") (pintype "passive"))
    )
    (net (code "109") (name "Net-(RX-PadA)") (class "Default")
      (node (ref "RX") (pin "A") (pinfunction "A_A") (pintype "passive"))
      (node (ref "R_RXLED") (pin "2") (pinfunction "2_2") (pintype "passive"))
    )
    (net (code "110") (name "Net-(R_TXLED-Pad2)") (class "Default")
      (node (ref "R_TXLED") (pin "2") (pinfunction "2_2") (pintype "passive"))
      (node (ref "TX") (pin "A") (pinfunction "A_A") (pintype "passive"))
    )
    (net (code "111") (name "Net-(SW-R1,C1)") (class "Default")
      (node (ref "M0R2") (pin "2") (pinfunction "2_2") (pintype "passive"))
      (node (ref "MOC1") (pin "1") (pinfunction "1_1") (pintype "passive"))
      (node (ref "SW") (pin "6") (pinfunction "R1,C1_6") (pintype "bidirectional"))
    )
    (net (code "112") (name "Net-(SW-R2)") (class "Default")
      (node (ref "M0R1") (pin "2") (pinfunction "2_2") (pintype "passive"))
      (node (ref "SW") (pin "1") (pinfunction "R2_1") (pintype "bidirectional"))
    )
    (net (code "113") (name "Net-(SW-VOUT,C1)") (class "Default")
      (node (ref "MOC1") (pin "2") (pinfunction "2_2") (pintype "passive"))
      (node (ref "SW") (pin "3") (pinfunction "VOUT,C1_3") (pintype "bidirectional"))
    )
    (net (code "114") (name "Net-(U1-RXLED)") (class "Default")
      (node (ref "RX") (pin "C") (pinfunction "C_C") (pintype "passive"))
      (node (ref "U1") (pin "22") (pinfunction "RXLED_22") (pintype "bidirectional"))
    )
    (net (code "115") (name "Net-(U1-TXLED)") (class "Default")
      (node (ref "TX") (pin "C") (pinfunction "C_C") (pintype "passive"))
      (node (ref "U1") (pin "23") (pinfunction "TXLED_23") (pintype "bidirectional"))
    )
    (net (code "116") (name "Net-(U1-USBDM)") (class "Default")
      (node (ref "JP5") (pin "D-") (pinfunction "D-_D-") (pintype "bidirectional"))
      (node (ref "U1") (pin "16") (pinfunction "USBDM_16") (pintype "bidirectional"))
    )
    (net (code "117") (name "Net-(U1-USBDP)") (class "Default")
      (node (ref "JP5") (pin "D+") (pinfunction "D+_D+") (pintype "bidirectional"))
      (node (ref "U1") (pin "15") (pinfunction "USBDP_15") (pintype "bidirectional"))
    )
    (net (code "118") (name "VCC") (class "Default")
      (node (ref "C11") (pin "2") (pinfunction "2_2") (pintype "passive"))
      (node (ref "COUT") (pin "1") (pinfunction "1_1") (pintype "passive"))
      (node (ref "D3") (pin "C") (pinfunction "C_C") (pintype "passive"))
      (node (ref "DECOUP") (pin "1") (pinfunction "1_1") (pintype "passive"))
      (node (ref "IC1") (pin "6") (pinfunction "SEN_6") (pintype "input"))
      (node (ref "IC3") (pin "10") (pinfunction "VCC_10") (pintype "power_in"))
      (node (ref "IC3") (pin "31") (pinfunction "VCC1_31") (pintype "power_in"))
      (node (ref "IC3") (pin "61") (pinfunction "VCC2_61") (pintype "power_in"))
      (node (ref "IC3") (pin "80") (pinfunction "VCC3_80") (pintype "power_in"))
      (node (ref "ISP") (pin "2") (pinfunction "VCC_2") (pintype "power_in"))
      (node (ref "J1") (pin "PWR") (pinfunction "PWR_PWR") (pintype "bidirectional"))
      (node (ref "LD0_SD") (pin "1") (pinfunction "VIN_1") (pintype "bidirectional"))
      (node (ref "LD0_SENSE") (pin "1") (pinfunction "VIN_1") (pintype "bidirectional"))
      (node (ref "L_LPF") (pin "2") (pinfunction "2_2") (pintype "passive"))
      (node (ref "M0R2") (pin "1") (pinfunction "1_1") (pintype "passive"))
      (node (ref "M1") (pin "4") (pinfunction "VIN,R1_4") (pintype "bidirectional"))
      (node (ref "M1R1") (pin "1") (pinfunction "1_1") (pintype "passive"))
      (node (ref "M2") (pin "4") (pinfunction "VIN,R1_4") (pintype "bidirectional"))
      (node (ref "M2R1") (pin "1") (pinfunction "1_1") (pintype "passive"))
      (node (ref "Q1") (pin "2") (pinfunction "S_2") (pintype "passive"))
      (node (ref "Q2") (pin "2") (pinfunction "S_2") (pintype "passive"))
      (node (ref "RSTAT") (pin "2") (pinfunction "2_2") (pintype "passive"))
      (node (ref "RTC_DS3234") (pin "4") (pinfunction "VCC_4") (pintype "bidirectional"))
      (node (ref "RTC_INT_PU") (pin "2") (pinfunction "2_2") (pintype "passive"))
      (node (ref "RTC_RST_PU") (pin "2") (pinfunction "2_2") (pintype "passive"))
      (node (ref "R_RESET") (pin "2") (pinfunction "2_2") (pintype "passive"))
      (node (ref "SCL_PU") (pin "2") (pinfunction "2_2") (pintype "passive"))
      (node (ref "SDA_PU") (pin "2") (pinfunction "2_2") (pintype "passive"))
      (node (ref "SW") (pin "4") (pinfunction "VIN,R1_4") (pintype "bidirectional"))
      (node (ref "U$11") (pin "6") (pinfunction "6_6") (pintype "passive"))
      (node (ref "U$11") (pin "7") (pinfunction "7_7") (pintype "passive"))
      (node (ref "U$14") (pin "5") (pinfunction "5_5") (pintype "passive"))
      (node (ref "VCC_VDIV_1") (pin "2") (pinfunction "2_2") (pintype "passive"))
    )
    (net (code "119") (name "VDD") (class "Default")
      (node (ref "C_LDO_SD") (pin "2") (pinfunction "2_2") (pintype "passive"))
      (node (ref "LD0_SD") (pin "5") (pinfunction "VOUT_5") (pintype "bidirectional"))
      (node (ref "LSHIFT") (pin "1") (pinfunction "VDD_1") (pintype "power_in"))
      (node (ref "SD") (pin "4") (pinfunction "VDD_4") (pintype "power_in"))
    )
    (net (code "120") (name "VUSB") (class "Default")
      (node (ref "JP5") (pin "VBUS") (pinfunction "VBUS_VBUS") (pintype "bidirectional"))
      (node (ref "Q2") (pin "3") (pinfunction "D_3") (pintype "passive"))
      (node (ref "R_RXLED") (pin "1") (pinfunction "1_1") (pintype "passive"))
      (node (ref "R_TXLED") (pin "1") (pinfunction "1_1") (pintype "passive"))
      (node (ref "U1") (pin "20") (pinfunction "VCC_20") (pintype "power_in"))
      (node (ref "U1") (pin "4") (pinfunction "VCCIO_4") (pintype "power_in"))
      (node (ref "USBD0") (pin "1") (pinfunction "1_1") (pintype "passive"))
      (node (ref "USBD1") (pin "A") (pinfunction "+_A") (pintype "passive"))
    )
    (net (code "121") (name "unconnected-(CLOCK_BATT-+1-Pad+$2)") (class "Default")
      (node (ref "CLOCK_BATT") (pin "+$2") (pinfunction "+1_+$2") (pintype "passive"))
    )
    (net (code "122") (name "unconnected-(IC3-(CLKO{slash}ICP3{slash}INT7)PE7-Pad9)") (class "Default")
      (node (ref "IC3") (pin "9") (pinfunction "(CLKO/ICP3/INT7)PE7_9") (pintype "bidirectional"))
    )
    (net (code "123") (name "unconnected-(IC3-(ICP1)PD4-Pad47)") (class "Default")
      (node (ref "IC3") (pin "47") (pinfunction "(ICP1)PD4_47") (pintype "bidirectional"))
    )
    (net (code "124") (name "unconnected-(IC3-(T1)PD6-Pad49)") (class "Default")
      (node (ref "IC3") (pin "49") (pinfunction "(T1)PD6_49") (pintype "bidirectional"))
    )
    (net (code "125") (name "unconnected-(IC3-(T3{slash}INT6)PE6-Pad8)") (class "Default")
      (node (ref "IC3") (pin "8") (pinfunction "(T3/INT6)PE6_8") (pintype "bidirectional"))
    )
    (net (code "126") (name "unconnected-(IC3-(TOSC1)PG4-Pad29)") (class "Default")
      (node (ref "IC3") (pin "29") (pinfunction "(TOSC1)PG4_29") (pintype "bidirectional"))
    )
    (net (code "127") (name "unconnected-(IC3-(TOSC2)PG3-Pad28)") (class "Default")
      (node (ref "IC3") (pin "28") (pinfunction "(TOSC2)PG3_28") (pintype "bidirectional"))
    )
    (net (code "128") (name "unconnected-(IC3-(XCK0{slash}AIN0)PE2-Pad4)") (class "Default")
      (node (ref "IC3") (pin "4") (pinfunction "(XCK0/AIN0)PE2_4") (pintype "bidirectional"))
    )
    (net (code "129") (name "unconnected-(IC3-(XCK1)PD5-Pad48)") (class "Default")
      (node (ref "IC3") (pin "48") (pinfunction "(XCK1)PD5_48") (pintype "bidirectional"))
    )
    (net (code "130") (name "unconnected-(IC3-PH2(XCK2)-Pad14)") (class "Default")
      (node (ref "IC3") (pin "14") (pinfunction "PH2(XCK2)_14") (pintype "bidirectional"))
    )
    (net (code "131") (name "unconnected-(IC3-PH7(T4)-Pad27)") (class "Default")
      (node (ref "IC3") (pin "27") (pinfunction "PH7(T4)_27") (pintype "bidirectional"))
    )
    (net (code "132") (name "unconnected-(IC3-PJ2(XCK3{slash}PCINT11)-Pad65)") (class "Default")
      (node (ref "IC3") (pin "65") (pinfunction "PJ2(XCK3/PCINT11)_65") (pintype "bidirectional"))
    )
    (net (code "133") (name "unconnected-(IC3-PJ3(PCINT12)-Pad66)") (class "Default")
      (node (ref "IC3") (pin "66") (pinfunction "PJ3(PCINT12)_66") (pintype "bidirectional"))
    )
    (net (code "134") (name "unconnected-(IC3-PJ4(PCINT13)-Pad67)") (class "Default")
      (node (ref "IC3") (pin "67") (pinfunction "PJ4(PCINT13)_67") (pintype "bidirectional"))
    )
    (net (code "135") (name "unconnected-(IC3-PJ5(PCINT14)-Pad68)") (class "Default")
      (node (ref "IC3") (pin "68") (pinfunction "PJ5(PCINT14)_68") (pintype "bidirectional"))
    )
    (net (code "136") (name "unconnected-(IC3-PJ6(PCINT15)-Pad69)") (class "Default")
      (node (ref "IC3") (pin "69") (pinfunction "PJ6(PCINT15)_69") (pintype "bidirectional"))
    )
    (net (code "137") (name "unconnected-(IC3-PJ7-Pad79)") (class "Default")
      (node (ref "IC3") (pin "79") (pinfunction "PJ7_79") (pintype "bidirectional"))
    )
    (net (code "138") (name "unconnected-(LD0_SD-BYP-Pad4)") (class "Default")
      (node (ref "LD0_SD") (pin "4") (pinfunction "BYP_4") (pintype "bidirectional"))
    )
    (net (code "139") (name "unconnected-(LD0_SENSE-BYP-Pad4)") (class "Default")
      (node (ref "LD0_SENSE") (pin "4") (pinfunction "BYP_4") (pintype "bidirectional"))
    )
    (net (code "140") (name "unconnected-(LSHIFTD-O-Pad10)") (class "Default")
      (node (ref "LSHIFT") (pin "10") (pinfunction "O_10") (pintype "output"))
    )
    (net (code "141") (name "unconnected-(LSHIFTE-O-Pad12)") (class "Default")
      (node (ref "LSHIFT") (pin "12") (pinfunction "O_12") (pintype "output"))
    )
    (net (code "142") (name "unconnected-(LSHIFTF-O-Pad15)") (class "Default")
      (node (ref "LSHIFT") (pin "15") (pinfunction "O_15") (pintype "output"))
    )
    (net (code "143") (name "unconnected-(RTC_DS3234-32KHZ-Pad3)") (class "Default")
      (node (ref "RTC_DS3234") (pin "3") (pinfunction "32KHZ_3") (pintype "bidirectional"))
    )
    (net (code "144") (name "unconnected-(SD-DAT1-Pad8)") (class "Default")
      (node (ref "SD") (pin "8") (pinfunction "DAT1_8") (pintype "bidirectional"))
    )
    (net (code "145") (name "unconnected-(SD-DAT2-Pad9)") (class "Default")
      (node (ref "SD") (pin "9") (pinfunction "DAT2_9") (pintype "bidirectional"))
    )
    (net (code "146") (name "unconnected-(SD-WRITE_PROTECT-PadWP)") (class "Default")
      (node (ref "SD") (pin "WP") (pinfunction "WRITE_PROTECT_WP") (pintype "passive"))
    )
    (net (code "147") (name "unconnected-(U$7-PadNC)") (class "Default")
      (node (ref "U$7") (pin "NC") (pinfunction "NC_NC") (pintype "bidirectional"))
    )
    (net (code "148") (name "unconnected-(U$9-PadNC)") (class "Default")
      (node (ref "U$9") (pin "NC") (pinfunction "NC_NC") (pintype "bidirectional"))
    )
    (net (code "149") (name "unconnected-(U1-3V3OUT-Pad17)") (class "Default")
      (node (ref "U1") (pin "17") (pinfunction "3V3OUT_17") (pintype "output"))
    )
    (net (code "150") (name "unconnected-(U1-RTS-Pad3)") (class "Default")
      (node (ref "U1") (pin "3") (pinfunction "RTS_3") (pintype "bidirectional"))
    )
  )
)
